# Processing.net
KiCad netlist of a schematic drawn in Altium Designer
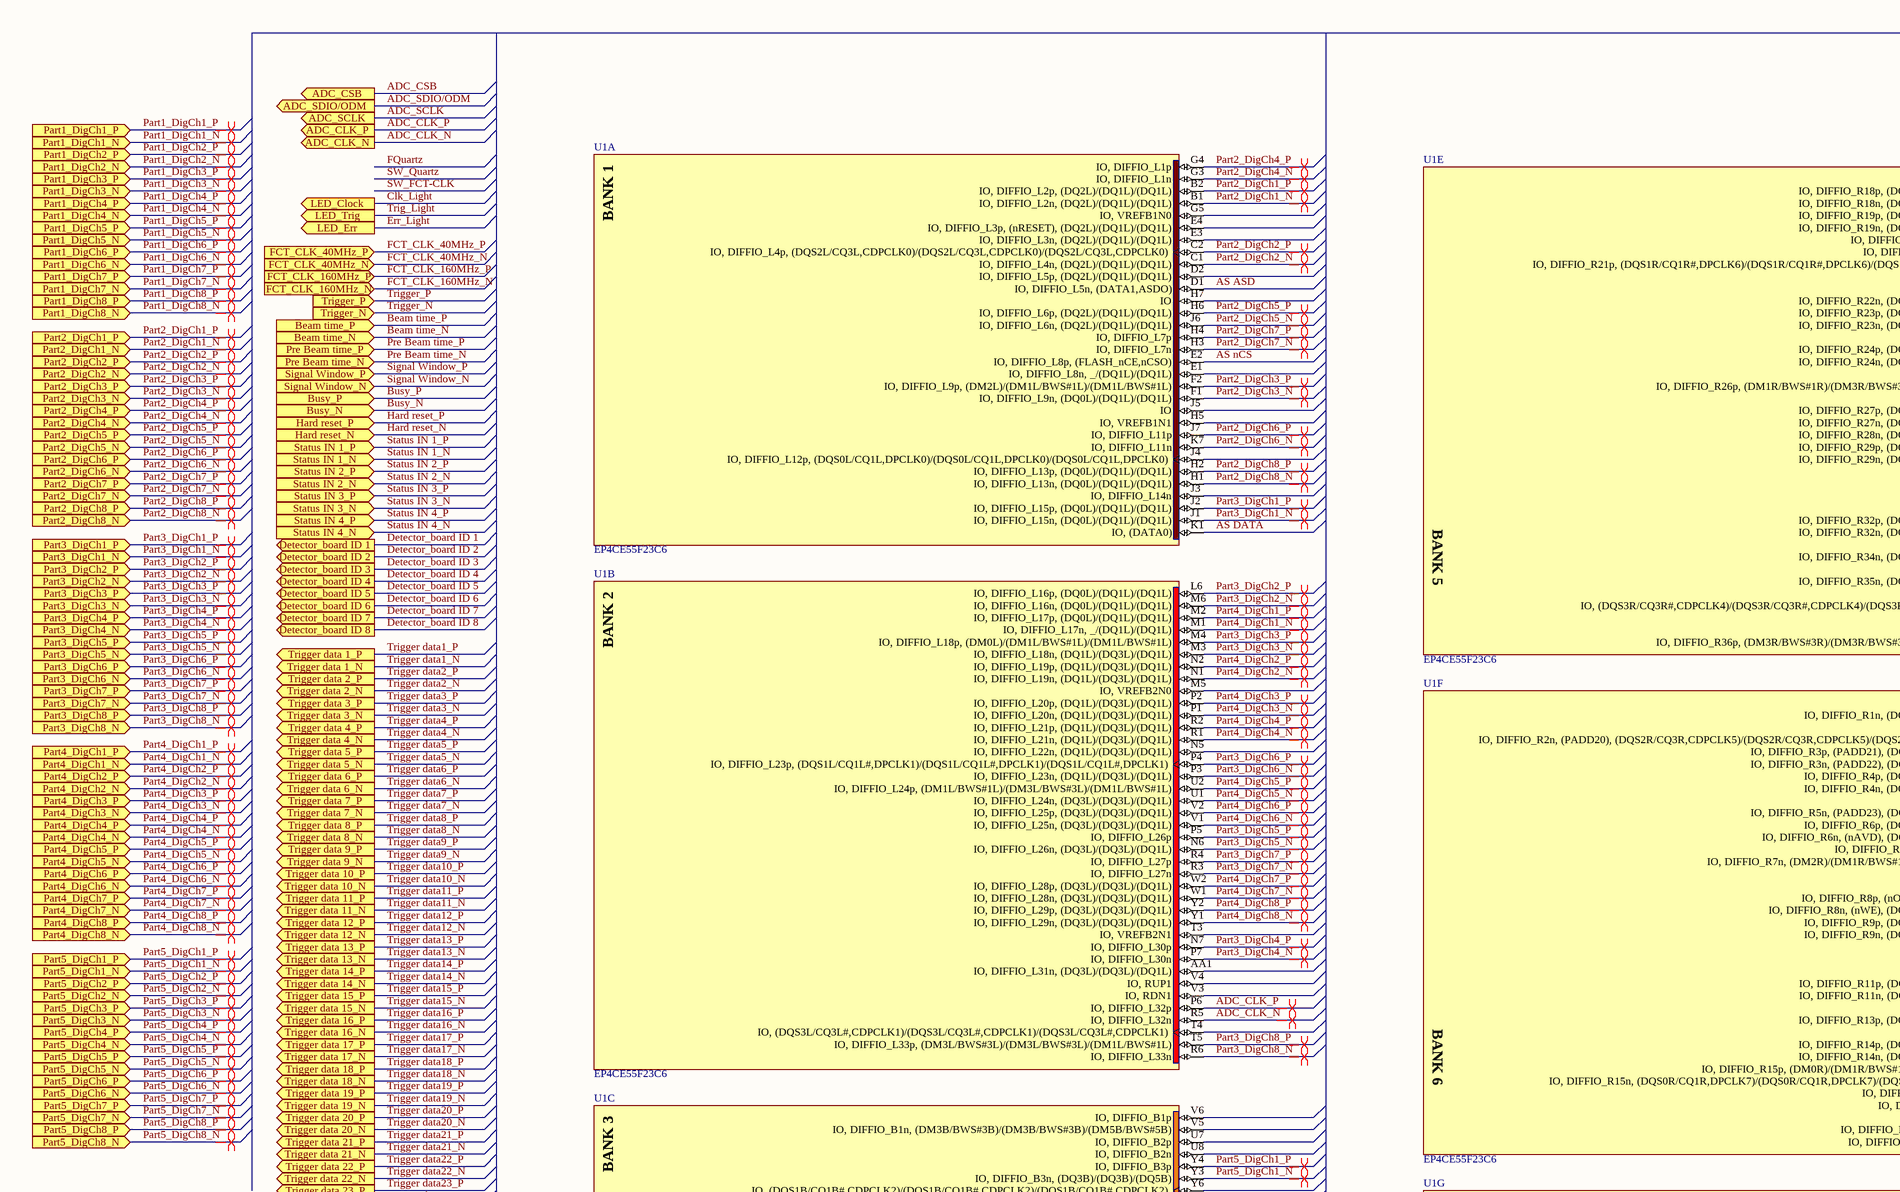
[diagram p0: Processing.SchDoc, top left]
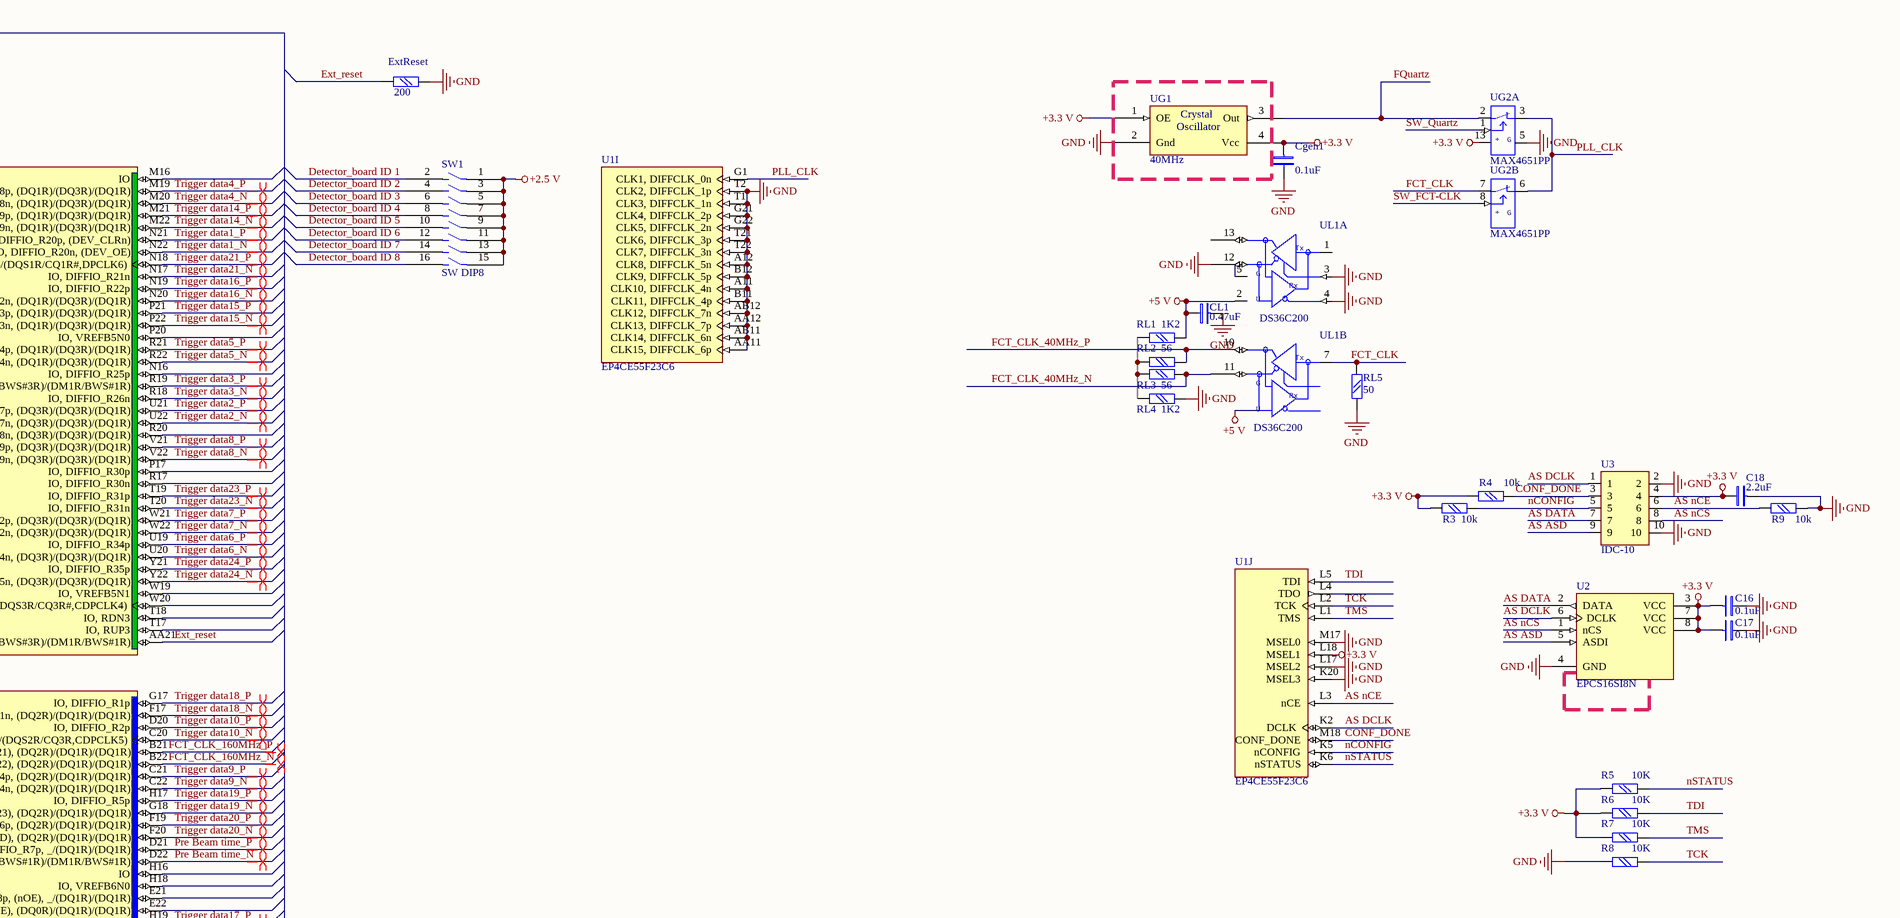
[diagram p1: Processing.SchDoc, top right]
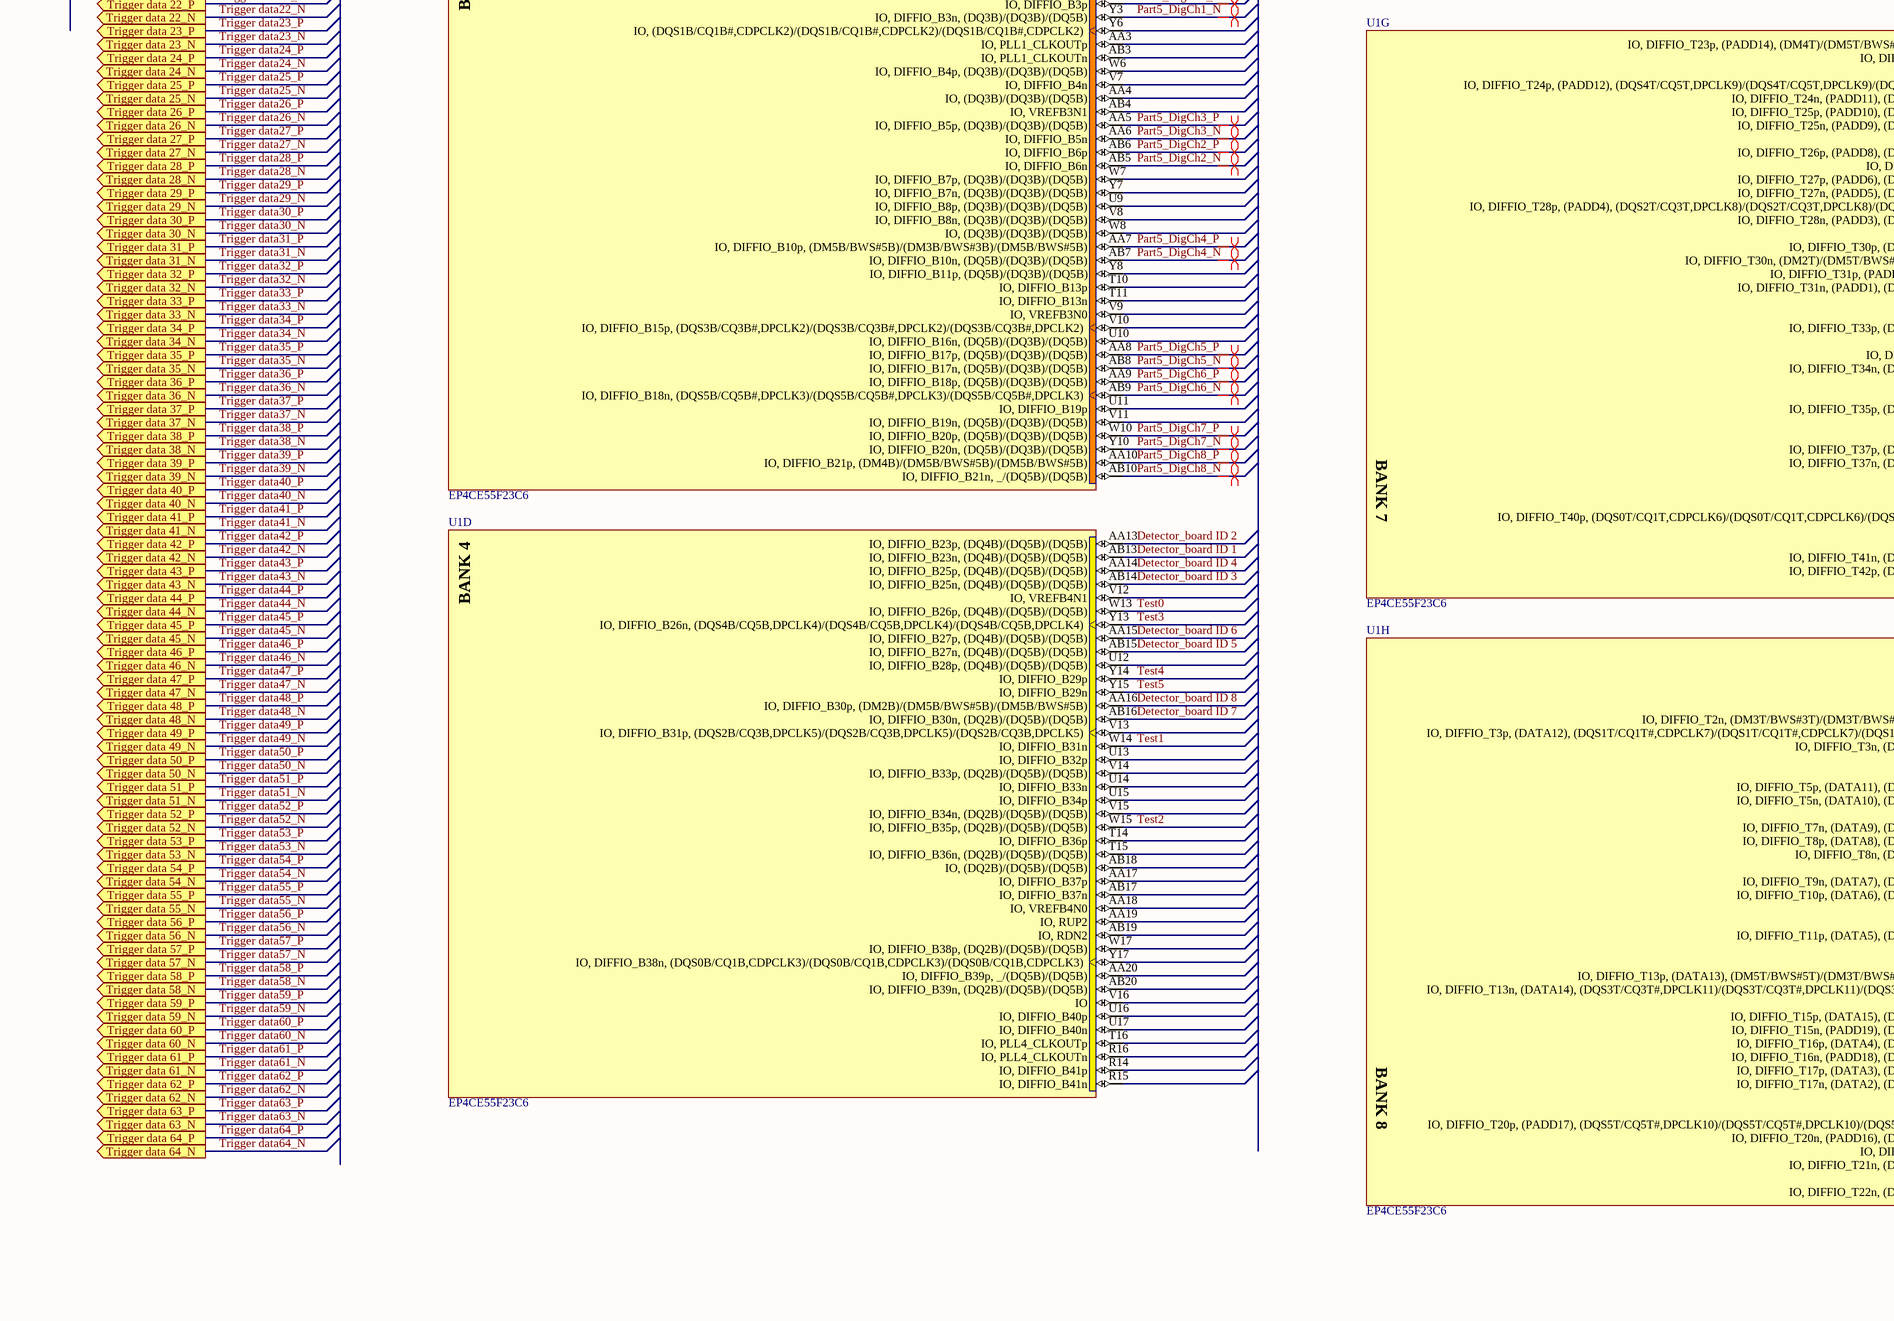
[diagram p2: Processing.SchDoc, bottom left]
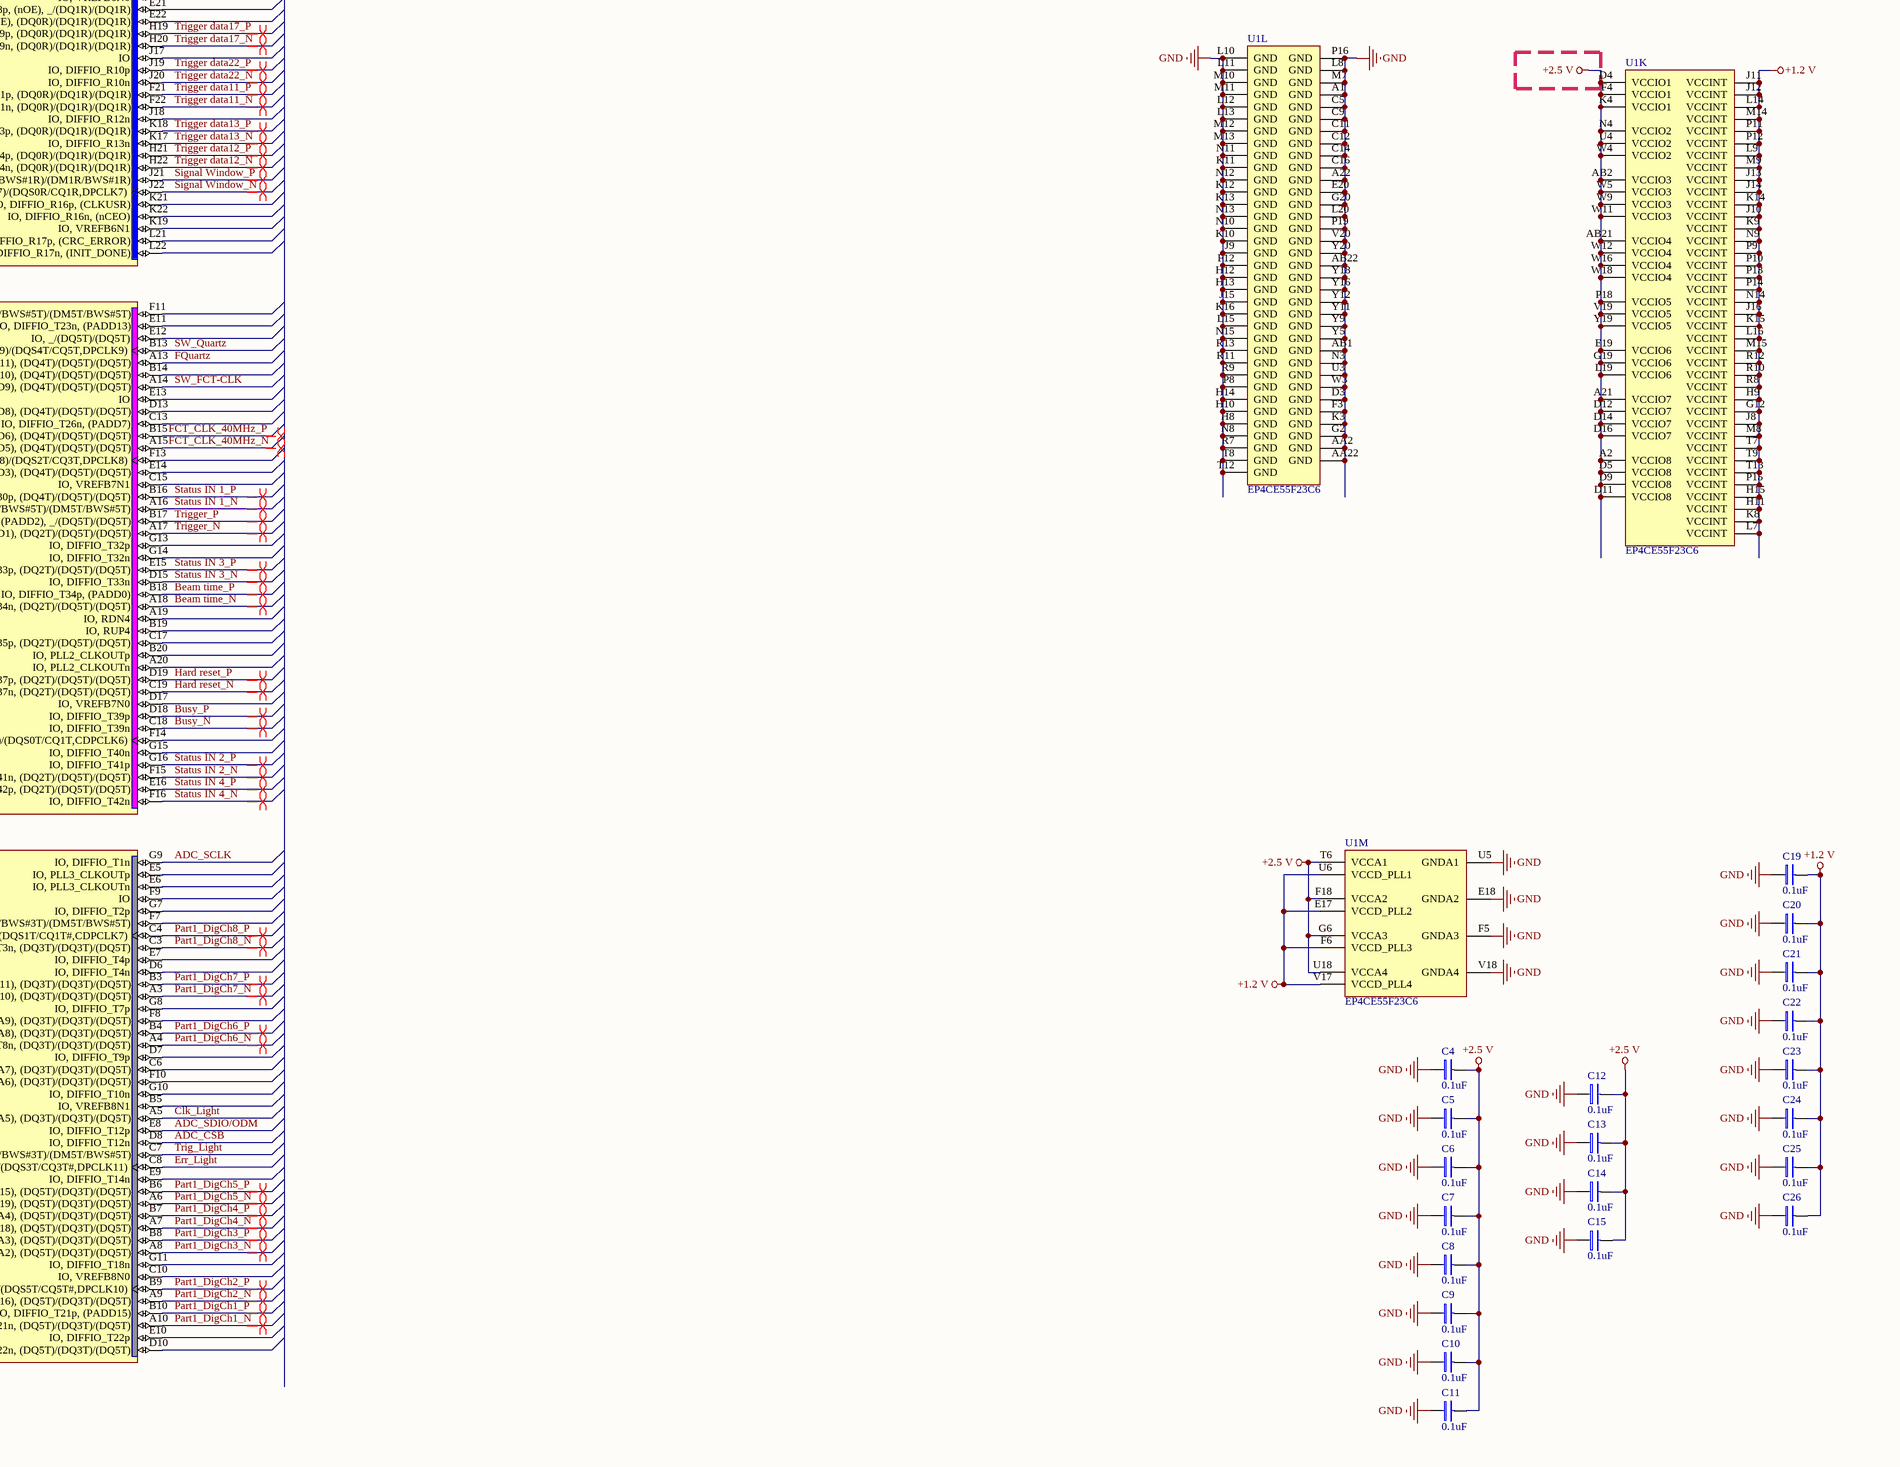
[diagram p3: Processing.SchDoc, bottom right]

(export (version "E")
  (design (tool "Eeschema 10.0.6"))
  (components
    (comp (ref "C4") (value "0.1uF") (footprint "chip0603") (libsource (lib "*") (part "C")))
    (comp (ref "C5") (value "0.1uF") (footprint "chip0603") (libsource (lib "*") (part "C")))
    (comp (ref "C6") (value "0.1uF") (footprint "chip0603") (libsource (lib "*") (part "C")))
    (comp (ref "C7") (value "0.1uF") (footprint "chip0603") (libsource (lib "*") (part "C")))
    (comp (ref "C8") (value "0.1uF") (footprint "chip0603") (libsource (lib "*") (part "C")))
    (comp (ref "C9") (value "0.1uF") (footprint "chip0603") (libsource (lib "*") (part "C")))
    (comp (ref "C10") (value "0.1uF") (footprint "chip0603") (libsource (lib "*") (part "C")))
    (comp (ref "C11") (value "0.1uF") (footprint "chip0603") (libsource (lib "*") (part "C")))
    (comp (ref "C12") (value "0.1uF") (footprint "chip0603") (libsource (lib "*") (part "C")))
    (comp (ref "C13") (value "0.1uF") (footprint "chip0603") (libsource (lib "*") (part "C")))
    (comp (ref "C14") (value "0.1uF") (footprint "chip0603") (libsource (lib "*") (part "C")))
    (comp (ref "C15") (value "0.1uF") (footprint "chip0603") (libsource (lib "*") (part "C")))
    (comp (ref "C16") (value "0.1uF") (footprint "chip0603") (libsource (lib "*") (part "C")))
    (comp (ref "C17") (value "0.1uF") (footprint "chip0603") (libsource (lib "*") (part "C")))
    (comp (ref "C18") (value "2.2uF") (footprint "chip0603") (libsource (lib "*") (part "C")))
    (comp (ref "C19") (value "0.1uF") (footprint "chip0603") (libsource (lib "*") (part "C")))
    (comp (ref "C20") (value "0.1uF") (footprint "chip0603") (libsource (lib "*") (part "C")))
    (comp (ref "C21") (value "0.1uF") (footprint "chip0603") (libsource (lib "*") (part "C")))
    (comp (ref "C22") (value "0.1uF") (footprint "chip0603") (libsource (lib "*") (part "C")))
    (comp (ref "C23") (value "0.1uF") (footprint "chip0603") (libsource (lib "*") (part "C")))
    (comp (ref "C24") (value "0.1uF") (footprint "chip0603") (libsource (lib "*") (part "C")))
    (comp (ref "C25") (value "0.1uF") (footprint "chip0603") (libsource (lib "*") (part "C")))
    (comp (ref "C26") (value "0.1uF") (footprint "chip0603") (libsource (lib "*") (part "C")))
    (comp (ref "Cgen1") (value "0.1uF") (footprint "chip0603") (libsource (lib "") (part "C_1")))
    (comp (ref "CL1") (value "0.47uF") (footprint "chip0603") (libsource (lib "") (part "C_1")))
    (comp (ref "ExtReset") (value "200") (footprint "chip0603") (libsource (lib "*") (part "R")))
    (comp (ref "R3") (value "10k") (footprint "chip0603") (libsource (lib "") (part "R_1")))
    (comp (ref "R4") (value "10k") (footprint "chip0603") (libsource (lib "") (part "R_1")))
    (comp (ref "R5") (value "10K") (footprint "chip0603") (libsource (lib "") (part "R_1")))
    (comp (ref "R6") (value "10K") (footprint "chip0603") (libsource (lib "") (part "R_1")))
    (comp (ref "R7") (value "10K") (footprint "chip0603") (libsource (lib "") (part "R_1")))
    (comp (ref "R8") (value "10K") (footprint "chip0603") (libsource (lib "") (part "R_1")))
    (comp (ref "R9") (value "10k") (footprint "chip0603") (libsource (lib "") (part "R_1")))
    (comp (ref "RL1") (value "1K2") (footprint "chip0603") (libsource (lib "*") (part "R")))
    (comp (ref "RL2") (value "56") (footprint "chip0603") (libsource (lib "*") (part "R")))
    (comp (ref "RL3") (value "56") (footprint "chip0603") (libsource (lib "*") (part "R")))
    (comp (ref "RL4") (value "1K2") (footprint "chip0603") (libsource (lib "*") (part "R")))
    (comp (ref "RL5") (value "50") (footprint "chip0603") (libsource (lib "*") (part "R")))
    (comp (ref "SW1") (value "SW DIP8") (footprint "SWD4-8") (libsource (lib "vDevice") (part "SW DIP8")))
    (comp (ref "U1")
      (value "EP4CE55F23C6")
      (footprint "FBGA484")
      (fields (field (name "PUBLISHER") "Altium Limited"))
      (libsource (lib "") (part "EP4CE55F23C6_1"))
    )
    (comp (ref "U2")
      (value "EPCS16SI8N")
      (footprint "SOIC8_N")
      (fields (field (name "PUBLISHER") "Altium Limited"))
      (libsource (lib "Altera EPCS Configuration Device") (part "EPCS4SI8N"))
    )
    (comp (ref "U3") (value "IDC-10") (footprint "IDC10") (libsource (lib "vDevice") (part "IDC-10")))
    (comp (ref "UG1")
      (value "40MHz")
      (footprint "SG-636")
      (description "Crystal Oscillator (SMD)")
      (libsource (lib "*") (part "SG-636"))
    )
    (comp (ref "UG2") (value "MAX4651PP") (footprint "16SOIC150") (libsource (lib "*") (part "MAX4651PP")))
    (comp (ref "UL1") (value "DS36C200") (footprint "14SO200") (libsource (lib "*") (part "DS36C200")))
  )
  (nets
    (net (code "1") (name "+1.2 V") (class "Default")
      (node (ref "C19") (pin "2") (pinfunction "2_2") (pintype "passive"))
      (node (ref "C20") (pin "2") (pinfunction "2_2") (pintype "passive"))
      (node (ref "C21") (pin "2") (pinfunction "2_2") (pintype "passive"))
      (node (ref "C22") (pin "2") (pinfunction "2_2") (pintype "passive"))
      (node (ref "C23") (pin "2") (pinfunction "2_2") (pintype "passive"))
      (node (ref "C24") (pin "2") (pinfunction "2_2") (pintype "passive"))
      (node (ref "C25") (pin "2") (pinfunction "2_2") (pintype "passive"))
      (node (ref "C26") (pin "2") (pinfunction "2_2") (pintype "passive"))
      (node (ref "U1") (pin "E17") (pinfunction "VCCD_PLL2_E17") (pintype "power_in"))
      (node (ref "U1") (pin "F6") (pinfunction "VCCD_PLL3_F6") (pintype "power_in"))
      (node (ref "U1") (pin "G12") (pinfunction "VCCINT_G12") (pintype "power_in"))
      (node (ref "U1") (pin "H11") (pinfunction "VCCINT_H11") (pintype "power_in"))
      (node (ref "U1") (pin "H15") (pinfunction "VCCINT_H15") (pintype "power_in"))
      (node (ref "U1") (pin "H9") (pinfunction "VCCINT_H9") (pintype "power_in"))
      (node (ref "U1") (pin "J10") (pinfunction "VCCINT_J10") (pintype "power_in"))
      (node (ref "U1") (pin "J11") (pinfunction "VCCINT_J11") (pintype "power_in"))
      (node (ref "U1") (pin "J12") (pinfunction "VCCINT_J12") (pintype "power_in"))
      (node (ref "U1") (pin "J13") (pinfunction "VCCINT_J13") (pintype "power_in"))
      (node (ref "U1") (pin "J14") (pinfunction "VCCINT_J14") (pintype "power_in"))
      (node (ref "U1") (pin "J16") (pinfunction "VCCINT_J16") (pintype "power_in"))
      (node (ref "U1") (pin "J8") (pinfunction "VCCINT_J8") (pintype "power_in"))
      (node (ref "U1") (pin "K14") (pinfunction "VCCINT_K14") (pintype "power_in"))
      (node (ref "U1") (pin "K15") (pinfunction "VCCINT_K15") (pintype "power_in"))
      (node (ref "U1") (pin "K8") (pinfunction "VCCINT_K8") (pintype "power_in"))
      (node (ref "U1") (pin "K9") (pinfunction "VCCINT_K9") (pintype "power_in"))
      (node (ref "U1") (pin "L14") (pinfunction "VCCINT_L14") (pintype "power_in"))
      (node (ref "U1") (pin "L16") (pinfunction "VCCINT_L16") (pintype "power_in"))
      (node (ref "U1") (pin "L7") (pinfunction "VCCINT_L7") (pintype "power_in"))
      (node (ref "U1") (pin "L9") (pinfunction "VCCINT_L9") (pintype "power_in"))
      (node (ref "U1") (pin "M14") (pinfunction "VCCINT_M14") (pintype "power_in"))
      (node (ref "U1") (pin "M15") (pinfunction "VCCINT_M15") (pintype "power_in"))
      (node (ref "U1") (pin "M8") (pinfunction "VCCINT_M8") (pintype "power_in"))
      (node (ref "U1") (pin "M9") (pinfunction "VCCINT_M9") (pintype "power_in"))
      (node (ref "U1") (pin "N14") (pinfunction "VCCINT_N14") (pintype "power_in"))
      (node (ref "U1") (pin "N9") (pinfunction "VCCINT_N9") (pintype "power_in"))
      (node (ref "U1") (pin "P10") (pinfunction "VCCINT_P10") (pintype "power_in"))
      (node (ref "U1") (pin "P11") (pinfunction "VCCINT_P11") (pintype "power_in"))
      (node (ref "U1") (pin "P12") (pinfunction "VCCINT_P12") (pintype "power_in"))
      (node (ref "U1") (pin "P13") (pinfunction "VCCINT_P13") (pintype "power_in"))
      (node (ref "U1") (pin "P14") (pinfunction "VCCINT_P14") (pintype "power_in"))
      (node (ref "U1") (pin "P15") (pinfunction "VCCINT_P15") (pintype "power_in"))
      (node (ref "U1") (pin "P9") (pinfunction "VCCINT_P9") (pintype "power_in"))
      (node (ref "U1") (pin "R10") (pinfunction "VCCINT_R10") (pintype "power_in"))
      (node (ref "U1") (pin "R12") (pinfunction "VCCINT_R12") (pintype "power_in"))
      (node (ref "U1") (pin "R8") (pinfunction "VCCINT_R8") (pintype "power_in"))
      (node (ref "U1") (pin "T13") (pinfunction "VCCINT_T13") (pintype "power_in"))
      (node (ref "U1") (pin "T7") (pinfunction "VCCINT_T7") (pintype "power_in"))
      (node (ref "U1") (pin "T9") (pinfunction "VCCINT_T9") (pintype "power_in"))
      (node (ref "U1") (pin "U6") (pinfunction "VCCD_PLL1_U6") (pintype "power_in"))
      (node (ref "U1") (pin "V17") (pinfunction "VCCD_PLL4_V17") (pintype "power_in"))
    )
    (net (code "2") (name "+2.5 V") (class "Default")
      (node (ref "C10") (pin "2") (pinfunction "2_2") (pintype "passive"))
      (node (ref "C11") (pin "2") (pinfunction "2_2") (pintype "passive"))
      (node (ref "C12") (pin "2") (pinfunction "2_2") (pintype "passive"))
      (node (ref "C13") (pin "2") (pinfunction "2_2") (pintype "passive"))
      (node (ref "C14") (pin "2") (pinfunction "2_2") (pintype "passive"))
      (node (ref "C15") (pin "2") (pinfunction "2_2") (pintype "passive"))
      (node (ref "C4") (pin "2") (pinfunction "2_2") (pintype "passive"))
      (node (ref "C5") (pin "2") (pinfunction "2_2") (pintype "passive"))
      (node (ref "C6") (pin "2") (pinfunction "2_2") (pintype "passive"))
      (node (ref "C7") (pin "2") (pinfunction "2_2") (pintype "passive"))
      (node (ref "C8") (pin "2") (pinfunction "2_2") (pintype "passive"))
      (node (ref "C9") (pin "2") (pinfunction "2_2") (pintype "passive"))
      (node (ref "SW1") (pin "1") (pinfunction "1_1") (pintype "passive"))
      (node (ref "SW1") (pin "11") (pinfunction "11_11") (pintype "passive"))
      (node (ref "SW1") (pin "13") (pinfunction "13_13") (pintype "passive"))
      (node (ref "SW1") (pin "15") (pinfunction "15_15") (pintype "passive"))
      (node (ref "SW1") (pin "3") (pinfunction "3_3") (pintype "passive"))
      (node (ref "SW1") (pin "5") (pinfunction "5_5") (pintype "passive"))
      (node (ref "SW1") (pin "7") (pinfunction "7_7") (pintype "passive"))
      (node (ref "SW1") (pin "9") (pinfunction "9_9") (pintype "passive"))
      (node (ref "U1") (pin "A2") (pinfunction "VCCIO8_A2") (pintype "power_in"))
      (node (ref "U1") (pin "A21") (pinfunction "VCCIO7_A21") (pintype "power_in"))
      (node (ref "U1") (pin "AB2") (pinfunction "VCCIO3_AB2") (pintype "power_in"))
      (node (ref "U1") (pin "AB21") (pinfunction "VCCIO4_AB21") (pintype "power_in"))
      (node (ref "U1") (pin "D11") (pinfunction "VCCIO8_D11") (pintype "power_in"))
      (node (ref "U1") (pin "D12") (pinfunction "VCCIO7_D12") (pintype "power_in"))
      (node (ref "U1") (pin "D14") (pinfunction "VCCIO7_D14") (pintype "power_in"))
      (node (ref "U1") (pin "D16") (pinfunction "VCCIO7_D16") (pintype "power_in"))
      (node (ref "U1") (pin "D4") (pinfunction "VCCIO1_D4") (pintype "power_in"))
      (node (ref "U1") (pin "D5") (pinfunction "VCCIO8_D5") (pintype "power_in"))
      (node (ref "U1") (pin "D9") (pinfunction "VCCIO8_D9") (pintype "power_in"))
      (node (ref "U1") (pin "E19") (pinfunction "VCCIO6_E19") (pintype "power_in"))
      (node (ref "U1") (pin "F18") (pinfunction "VCCA2_F18") (pintype "power_in"))
      (node (ref "U1") (pin "F4") (pinfunction "VCCIO1_F4") (pintype "power_in"))
      (node (ref "U1") (pin "G19") (pinfunction "VCCIO6_G19") (pintype "power_in"))
      (node (ref "U1") (pin "G6") (pinfunction "VCCA3_G6") (pintype "power_in"))
      (node (ref "U1") (pin "K4") (pinfunction "VCCIO1_K4") (pintype "power_in"))
      (node (ref "U1") (pin "L19") (pinfunction "VCCIO6_L19") (pintype "power_in"))
      (node (ref "U1") (pin "N4") (pinfunction "VCCIO2_N4") (pintype "power_in"))
      (node (ref "U1") (pin "P18") (pinfunction "VCCIO5_P18") (pintype "power_in"))
      (node (ref "U1") (pin "T6") (pinfunction "VCCA1_T6") (pintype "power_in"))
      (node (ref "U1") (pin "U18") (pinfunction "VCCA4_U18") (pintype "power_in"))
      (node (ref "U1") (pin "U4") (pinfunction "VCCIO2_U4") (pintype "power_in"))
      (node (ref "U1") (pin "V19") (pinfunction "VCCIO5_V19") (pintype "power_in"))
      (node (ref "U1") (pin "W11") (pinfunction "VCCIO3_W11") (pintype "power_in"))
      (node (ref "U1") (pin "W12") (pinfunction "VCCIO4_W12") (pintype "power_in"))
      (node (ref "U1") (pin "W16") (pinfunction "VCCIO4_W16") (pintype "power_in"))
      (node (ref "U1") (pin "W18") (pinfunction "VCCIO4_W18") (pintype "power_in"))
      (node (ref "U1") (pin "W4") (pinfunction "VCCIO2_W4") (pintype "power_in"))
      (node (ref "U1") (pin "W5") (pinfunction "VCCIO3_W5") (pintype "power_in"))
      (node (ref "U1") (pin "W9") (pinfunction "VCCIO3_W9") (pintype "power_in"))
      (node (ref "U1") (pin "Y19") (pinfunction "VCCIO5_Y19") (pintype "power_in"))
    )
    (net (code "3") (name "+3.3 V") (class "Default")
      (node (ref "C16") (pin "2") (pinfunction "2_2") (pintype "passive"))
      (node (ref "C17") (pin "2") (pinfunction "2_2") (pintype "passive"))
      (node (ref "C18") (pin "1") (pinfunction "1_1") (pintype "passive"))
      (node (ref "Cgen1") (pin "2") (pinfunction "2_2") (pintype "passive"))
      (node (ref "R3") (pin "1") (pinfunction "1_1") (pintype "passive"))
      (node (ref "R4") (pin "1") (pinfunction "1_1") (pintype "passive"))
      (node (ref "R5") (pin "1") (pinfunction "1_1") (pintype "passive"))
      (node (ref "R6") (pin "1") (pinfunction "1_1") (pintype "passive"))
      (node (ref "R7") (pin "1") (pinfunction "1_1") (pintype "passive"))
      (node (ref "U1") (pin "L18") (pinfunction "MSEL1_L18") (pintype "input"))
      (node (ref "U2") (pin "3") (pinfunction "VCC_3") (pintype "power_in"))
      (node (ref "U2") (pin "7") (pinfunction "VCC_7") (pintype "power_in"))
      (node (ref "U2") (pin "8") (pinfunction "VCC_8") (pintype "power_in"))
      (node (ref "U3") (pin "4") (pinfunction "4_4") (pintype "bidirectional"))
      (node (ref "UG1") (pin "1") (pinfunction "OE_1") (pintype "input"))
      (node (ref "UG1") (pin "4") (pinfunction "Vcc_4") (pintype "power_in"))
      (node (ref "UG2") (pin "13") (pinfunction "VCC_13") (pintype "passive"))
    )
    (net (code "4") (name "+5 V") (class "Default")
      (node (ref "CL1") (pin "1") (pinfunction "1_1") (pintype "passive"))
      (node (ref "RL1") (pin "2") (pinfunction "2_2") (pintype "passive"))
      (node (ref "UL1") (pin "2") (pinfunction "VCC_2") (pintype "passive"))
    )
    (net (code "5") (name "/ADC_CLK_N") (class "Default")
      (node (ref "U1") (pin "R5") (pinfunction "IO,_DIFFIO_L32n_R5") (pintype "bidirectional"))
    )
    (net (code "6") (name "/ADC_CLK_P") (class "Default")
      (node (ref "U1") (pin "P6") (pinfunction "IO,_DIFFIO_L32p_P6") (pintype "bidirectional"))
    )
    (net (code "7") (name "/ADC_CSB") (class "Default")
      (node (ref "U1") (pin "D8") (pinfunction "IO,_DIFFIO_T12n_D8") (pintype "bidirectional"))
    )
    (net (code "8") (name "/ADC_SCLK") (class "Default")
      (node (ref "U1") (pin "G9") (pinfunction "IO,_DIFFIO_T1n_G9") (pintype "bidirectional"))
    )
    (net (code "9") (name "/ADC_SDIO{slash}ODM") (class "Default")
      (node (ref "U1") (pin "E8") (pinfunction "IO,_DIFFIO_T12p_E8") (pintype "bidirectional"))
    )
    (net (code "10") (name "/AS ASD") (class "Default")
      (node (ref "U1") (pin "D1") (pinfunction "IO,_DIFFIO_L5n,_(DATA1,ASDO)_D1") (pintype "bidirectional"))
      (node (ref "U2") (pin "5") (pinfunction "ASDI_5") (pintype "input"))
      (node (ref "U3") (pin "9") (pinfunction "9_9") (pintype "bidirectional"))
    )
    (net (code "11") (name "/AS DATA") (class "Default")
      (node (ref "U1") (pin "K1") (pinfunction "IO,_(DATA0)_K1") (pintype "bidirectional"))
      (node (ref "U2") (pin "2") (pinfunction "DATA_2") (pintype "output"))
      (node (ref "U3") (pin "7") (pinfunction "7_7") (pintype "bidirectional"))
    )
    (net (code "12") (name "/AS DCLK") (class "Default")
      (node (ref "U1") (pin "K2") (pinfunction "DCLK_K2") (pintype "bidirectional"))
      (node (ref "U2") (pin "6") (pinfunction "DCLK_6") (pintype "input"))
      (node (ref "U3") (pin "1") (pinfunction "1_1") (pintype "bidirectional"))
    )
    (net (code "13") (name "/AS nCE") (class "Default")
      (node (ref "R9") (pin "1") (pinfunction "1_1") (pintype "passive"))
      (node (ref "U1") (pin "L3") (pinfunction "nCE_L3") (pintype "input"))
      (node (ref "U3") (pin "6") (pinfunction "6_6") (pintype "bidirectional"))
    )
    (net (code "14") (name "/AS nCS") (class "Default")
      (node (ref "U1") (pin "E2") (pinfunction "IO,_DIFFIO_L8p,_(FLASH_nCE,nCSO)_E2") (pintype "bidirectional"))
      (node (ref "U2") (pin "1") (pinfunction "nCS_1") (pintype "input"))
      (node (ref "U3") (pin "8") (pinfunction "8_8") (pintype "bidirectional"))
    )
    (net (code "15") (name "/Beam time_N") (class "Default")
      (node (ref "U1") (pin "A18") (pinfunction "IO,_DIFFIO_T34n,_(DQ2T)/(DQ5T)/(DQ5T)_A18") (pintype "bidirectional"))
    )
    (net (code "16") (name "/Beam time_P") (class "Default")
      (node (ref "U1") (pin "B18") (pinfunction "IO,_DIFFIO_T34p,_(PADD0)_B18") (pintype "bidirectional"))
    )
    (net (code "17") (name "/Busy_N") (class "Default")
      (node (ref "U1") (pin "C18") (pinfunction "IO,_DIFFIO_T39n_C18") (pintype "bidirectional"))
    )
    (net (code "18") (name "/Busy_P") (class "Default")
      (node (ref "U1") (pin "D18") (pinfunction "IO,_DIFFIO_T39p_D18") (pintype "bidirectional"))
    )
    (net (code "19") (name "/CONF_DONE") (class "Default")
      (node (ref "R4") (pin "2") (pinfunction "2_2") (pintype "passive"))
      (node (ref "U1") (pin "M18") (pinfunction "CONF_DONE_M18") (pintype "bidirectional"))
      (node (ref "U3") (pin "3") (pinfunction "3_3") (pintype "bidirectional"))
    )
    (net (code "20") (name "/Clk_Light") (class "Default")
      (node (ref "U1") (pin "A5") (pinfunction "IO,_DIFFIO_T11p,_(DATA5),_(DQ3T)/(DQ3T)/(DQ5T)_A5") (pintype "bidirectional"))
    )
    (net (code "21") (name "/Detector_board ID 1") (class "Default")
      (node (ref "SW1") (pin "2") (pinfunction "2_2") (pintype "passive"))
      (node (ref "U1") (pin "AB13") (pinfunction "IO,_DIFFIO_B23n,_(DQ4B)/(DQ5B)/(DQ5B)_AB13") (pintype "bidirectional"))
    )
    (net (code "22") (name "/Detector_board ID 2") (class "Default")
      (node (ref "SW1") (pin "4") (pinfunction "4_4") (pintype "passive"))
      (node (ref "U1") (pin "AA13") (pinfunction "IO,_DIFFIO_B23p,_(DQ4B)/(DQ5B)/(DQ5B)_AA13") (pintype "bidirectional"))
    )
    (net (code "23") (name "/Detector_board ID 3") (class "Default")
      (node (ref "SW1") (pin "6") (pinfunction "6_6") (pintype "passive"))
      (node (ref "U1") (pin "AB14") (pinfunction "IO,_DIFFIO_B25n,_(DQ4B)/(DQ5B)/(DQ5B)_AB14") (pintype "bidirectional"))
    )
    (net (code "24") (name "/Detector_board ID 4") (class "Default")
      (node (ref "SW1") (pin "8") (pinfunction "8_8") (pintype "passive"))
      (node (ref "U1") (pin "AA14") (pinfunction "IO,_DIFFIO_B25p,_(DQ4B)/(DQ5B)/(DQ5B)_AA14") (pintype "bidirectional"))
    )
    (net (code "25") (name "/Detector_board ID 5") (class "Default")
      (node (ref "SW1") (pin "10") (pinfunction "10_10") (pintype "passive"))
      (node (ref "U1") (pin "AB15") (pinfunction "IO,_DIFFIO_B27n,_(DQ4B)/(DQ5B)/(DQ5B)_AB15") (pintype "bidirectional"))
    )
    (net (code "26") (name "/Detector_board ID 6") (class "Default")
      (node (ref "SW1") (pin "12") (pinfunction "12_12") (pintype "passive"))
      (node (ref "U1") (pin "AA15") (pinfunction "IO,_DIFFIO_B27p,_(DQ4B)/(DQ5B)/(DQ5B)_AA15") (pintype "bidirectional"))
    )
    (net (code "27") (name "/Detector_board ID 7") (class "Default")
      (node (ref "SW1") (pin "14") (pinfunction "14_14") (pintype "passive"))
      (node (ref "U1") (pin "AB16") (pinfunction "IO,_DIFFIO_B30n,_(DQ2B)/(DQ5B)/(DQ5B)_AB16") (pintype "bidirectional"))
    )
    (net (code "28") (name "/Detector_board ID 8") (class "Default")
      (node (ref "SW1") (pin "16") (pinfunction "16_16") (pintype "passive"))
      (node (ref "U1") (pin "AA16") (pinfunction "IO,_DIFFIO_B30p,_(DM2B)/(DM5B/BWS#5B)/(DM5B/BWS#5B)_AA16") (pintype "bidirectional"))
    )
    (net (code "29") (name "/Err_Light") (class "Default")
      (node (ref "U1") (pin "C8") (pinfunction "IO,_DIFFIO_T13n,_(DATA14),_(DQS3T/CQ3T#,DPCLK11)/(DQS3T/CQ3T#,DPCLK11)/(DQS3T/CQ3T#,DPCLK11)_C8") (pintype "bidirectional"))
    )
    (net (code "30") (name "/Ext_reset") (class "Default")
      (node (ref "ExtReset") (pin "1") (pinfunction "1_1") (pintype "passive"))
      (node (ref "U1") (pin "AA21") (pinfunction "IO,_DIFFIO_R36p,_(DM3R/BWS#3R)/(DM3R/BWS#3R)/(DM1R/BWS#1R)_AA21") (pintype "bidirectional"))
    )
    (net (code "31") (name "/FCT_CLK") (class "Default")
      (node (ref "RL5") (pin "1") (pinfunction "1_1") (pintype "passive"))
      (node (ref "UG2") (pin "7") (pinfunction "IN_7") (pintype "bidirectional"))
      (node (ref "UL1") (pin "7") (pinfunction "DATA_7") (pintype "bidirectional"))
    )
    (net (code "32") (name "/FCT_CLK_40MHz_N") (class "Default")
      (node (ref "RL3") (pin "2") (pinfunction "2_2") (pintype "passive"))
      (node (ref "U1") (pin "A15") (pinfunction "IO,_DIFFIO_T27n,_(PADD5),_(DQ4T)/(DQ5T)/(DQ5T)_A15") (pintype "bidirectional"))
      (node (ref "UL1") (pin "11") (pinfunction "WIRE-_11") (pintype "bidirectional"))
    )
    (net (code "33") (name "/FCT_CLK_40MHz_P") (class "Default")
      (node (ref "RL2") (pin "2") (pinfunction "2_2") (pintype "passive"))
      (node (ref "U1") (pin "B15") (pinfunction "IO,_DIFFIO_T27p,_(PADD6),_(DQ4T)/(DQ5T)/(DQ5T)_B15") (pintype "bidirectional"))
      (node (ref "UL1") (pin "10") (pinfunction "WIRE+_10") (pintype "bidirectional"))
    )
    (net (code "34") (name "/FCT_CLK_160MHz_N") (class "Default")
      (node (ref "U1") (pin "B22") (pinfunction "IO,_DIFFIO_R3n,_(PADD22),_(DQ2R)/(DQ1R)/(DQ1R)_B22") (pintype "bidirectional"))
    )
    (net (code "35") (name "/FCT_CLK_160MHz_P") (class "Default")
      (node (ref "U1") (pin "B21") (pinfunction "IO,_DIFFIO_R3p,_(PADD21),_(DQ2R)/(DQ1R)/(DQ1R)_B21") (pintype "bidirectional"))
    )
    (net (code "36") (name "/FQuartz") (class "Default")
      (node (ref "U1") (pin "A13") (pinfunction "IO,_DIFFIO_T24n,_(PADD11),_(DQ4T)/(DQ5T)/(DQ5T)_A13") (pintype "bidirectional"))
      (node (ref "UG1") (pin "3") (pinfunction "Out_3") (pintype "output"))
      (node (ref "UG2") (pin "2") (pinfunction "IN_2") (pintype "bidirectional"))
    )
    (net (code "37") (name "/Hard reset_N") (class "Default")
      (node (ref "U1") (pin "C19") (pinfunction "IO,_DIFFIO_T37n,_(DQ2T)/(DQ5T)/(DQ5T)_C19") (pintype "bidirectional"))
    )
    (net (code "38") (name "/Hard reset_P") (class "Default")
      (node (ref "U1") (pin "D19") (pinfunction "IO,_DIFFIO_T37p,_(DQ2T)/(DQ5T)/(DQ5T)_D19") (pintype "bidirectional"))
    )
    (net (code "39") (name "/PLL_CLK") (class "Default")
      (node (ref "U1") (pin "G1") (pinfunction "CLK1,_DIFFCLK_0n_G1") (pintype "input"))
      (node (ref "UG2") (pin "3") (pinfunction "OUT_3") (pintype "bidirectional"))
      (node (ref "UG2") (pin "6") (pinfunction "OUT_6") (pintype "bidirectional"))
    )
    (net (code "40") (name "/Part1_DigCh1_N") (class "Default")
      (node (ref "U1") (pin "A10") (pinfunction "IO,_DIFFIO_T21n,_(DQ5T)/(DQ3T)/(DQ5T)_A10") (pintype "bidirectional"))
    )
    (net (code "41") (name "/Part1_DigCh1_P") (class "Default")
      (node (ref "U1") (pin "B10") (pinfunction "IO,_DIFFIO_T21p,_(PADD15)_B10") (pintype "bidirectional"))
    )
    (net (code "42") (name "/Part1_DigCh2_N") (class "Default")
      (node (ref "U1") (pin "A9") (pinfunction "IO,_DIFFIO_T20n,_(PADD16),_(DQ5T)/(DQ3T)/(DQ5T)_A9") (pintype "bidirectional"))
    )
    (net (code "43") (name "/Part1_DigCh2_P") (class "Default")
      (node (ref "U1") (pin "B9") (pinfunction "IO,_DIFFIO_T20p,_(PADD17),_(DQS5T/CQ5T#,DPCLK10)/(DQS5T/CQ5T#,DPCLK10)/(DQS5T/CQ5T#,DPCLK10)_B9") (pintype "bidirectional"))
    )
    (net (code "44") (name "/Part1_DigCh3_N") (class "Default")
      (node (ref "U1") (pin "A8") (pinfunction "IO,_DIFFIO_T17n,_(DATA2),_(DQ5T)/(DQ3T)/(DQ5T)_A8") (pintype "bidirectional"))
    )
    (net (code "45") (name "/Part1_DigCh3_P") (class "Default")
      (node (ref "U1") (pin "B8") (pinfunction "IO,_DIFFIO_T17p,_(DATA3),_(DQ5T)/(DQ3T)/(DQ5T)_B8") (pintype "bidirectional"))
    )
    (net (code "46") (name "/Part1_DigCh4_N") (class "Default")
      (node (ref "U1") (pin "A7") (pinfunction "IO,_DIFFIO_T16n,_(PADD18),_(DQ5T)/(DQ3T)/(DQ5T)_A7") (pintype "bidirectional"))
    )
    (net (code "47") (name "/Part1_DigCh4_P") (class "Default")
      (node (ref "U1") (pin "B7") (pinfunction "IO,_DIFFIO_T16p,_(DATA4),_(DQ5T)/(DQ3T)/(DQ5T)_B7") (pintype "bidirectional"))
    )
    (net (code "48") (name "/Part1_DigCh5_N") (class "Default")
      (node (ref "U1") (pin "A6") (pinfunction "IO,_DIFFIO_T15n,_(PADD19),_(DQ5T)/(DQ3T)/(DQ5T)_A6") (pintype "bidirectional"))
    )
    (net (code "49") (name "/Part1_DigCh5_P") (class "Default")
      (node (ref "U1") (pin "B6") (pinfunction "IO,_DIFFIO_T15p,_(DATA15),_(DQ5T)/(DQ3T)/(DQ5T)_B6") (pintype "bidirectional"))
    )
    (net (code "50") (name "/Part1_DigCh6_N") (class "Default")
      (node (ref "U1") (pin "A4") (pinfunction "IO,_DIFFIO_T8n,_(DQ3T)/(DQ3T)/(DQ5T)_A4") (pintype "bidirectional"))
    )
    (net (code "51") (name "/Part1_DigCh6_P") (class "Default")
      (node (ref "U1") (pin "B4") (pinfunction "IO,_DIFFIO_T8p,_(DATA8),_(DQ3T)/(DQ3T)/(DQ5T)_B4") (pintype "bidirectional"))
    )
    (net (code "52") (name "/Part1_DigCh7_N") (class "Default")
      (node (ref "U1") (pin "A3") (pinfunction "IO,_DIFFIO_T5n,_(DATA10),_(DQ3T)/(DQ3T)/(DQ5T)_A3") (pintype "bidirectional"))
    )
    (net (code "53") (name "/Part1_DigCh7_P") (class "Default")
      (node (ref "U1") (pin "B3") (pinfunction "IO,_DIFFIO_T5p,_(DATA11),_(DQ3T)/(DQ3T)/(DQ5T)_B3") (pintype "bidirectional"))
    )
    (net (code "54") (name "/Part1_DigCh8_N") (class "Default")
      (node (ref "U1") (pin "C3") (pinfunction "IO,_DIFFIO_T3n,_(DQ3T)/(DQ3T)/(DQ5T)_C3") (pintype "bidirectional"))
    )
    (net (code "55") (name "/Part1_DigCh8_P") (class "Default")
      (node (ref "U1") (pin "C4") (pinfunction "IO,_DIFFIO_T3p,_(DATA12),_(DQS1T/CQ1T#,CDPCLK7)/(DQS1T/CQ1T#,CDPCLK7)/(DQS1T/CQ1T#,CDPCLK7)_C4") (pintype "bidirectional"))
    )
    (net (code "56") (name "/Part2_DigCh1_N") (class "Default")
      (node (ref "U1") (pin "B1") (pinfunction "IO,_DIFFIO_L2n,_(DQ2L)/(DQ1L)/(DQ1L)_B1") (pintype "bidirectional"))
    )
    (net (code "57") (name "/Part2_DigCh1_P") (class "Default")
      (node (ref "U1") (pin "B2") (pinfunction "IO,_DIFFIO_L2p,_(DQ2L)/(DQ1L)/(DQ1L)_B2") (pintype "bidirectional"))
    )
    (net (code "58") (name "/Part2_DigCh2_N") (class "Default")
      (node (ref "U1") (pin "C1") (pinfunction "IO,_DIFFIO_L4n,_(DQ2L)/(DQ1L)/(DQ1L)_C1") (pintype "bidirectional"))
    )
    (net (code "59") (name "/Part2_DigCh2_P") (class "Default")
      (node (ref "U1") (pin "C2") (pinfunction "IO,_DIFFIO_L4p,_(DQS2L/CQ3L,CDPCLK0)/(DQS2L/CQ3L,CDPCLK0)/(DQS2L/CQ3L,CDPCLK0)_C2") (pintype "bidirectional"))
    )
    (net (code "60") (name "/Part2_DigCh3_N") (class "Default")
      (node (ref "U1") (pin "F1") (pinfunction "IO,_DIFFIO_L9n,_(DQ0L)/(DQ1L)/(DQ1L)_F1") (pintype "bidirectional"))
    )
    (net (code "61") (name "/Part2_DigCh3_P") (class "Default")
      (node (ref "U1") (pin "F2") (pinfunction "IO,_DIFFIO_L9p,_(DM2L)/(DM1L/BWS#1L)/(DM1L/BWS#1L)_F2") (pintype "bidirectional"))
    )
    (net (code "62") (name "/Part2_DigCh4_N") (class "Default")
      (node (ref "U1") (pin "G3") (pinfunction "IO,_DIFFIO_L1n_G3") (pintype "bidirectional"))
    )
    (net (code "63") (name "/Part2_DigCh4_P") (class "Default")
      (node (ref "U1") (pin "G4") (pinfunction "IO,_DIFFIO_L1p_G4") (pintype "bidirectional"))
    )
    (net (code "64") (name "/Part2_DigCh5_N") (class "Default")
      (node (ref "U1") (pin "J6") (pinfunction "IO,_DIFFIO_L6n,_(DQ2L)/(DQ1L)/(DQ1L)_J6") (pintype "bidirectional"))
    )
    (net (code "65") (name "/Part2_DigCh5_P") (class "Default")
      (node (ref "U1") (pin "H6") (pinfunction "IO,_DIFFIO_L6p,_(DQ2L)/(DQ1L)/(DQ1L)_H6") (pintype "bidirectional"))
    )
    (net (code "66") (name "/Part2_DigCh6_N") (class "Default")
      (node (ref "U1") (pin "K7") (pinfunction "IO,_DIFFIO_L11n_K7") (pintype "bidirectional"))
    )
    (net (code "67") (name "/Part2_DigCh6_P") (class "Default")
      (node (ref "U1") (pin "J7") (pinfunction "IO,_DIFFIO_L11p_J7") (pintype "bidirectional"))
    )
    (net (code "68") (name "/Part2_DigCh7_N") (class "Default")
      (node (ref "U1") (pin "H3") (pinfunction "IO,_DIFFIO_L7n_H3") (pintype "bidirectional"))
    )
    (net (code "69") (name "/Part2_DigCh7_P") (class "Default")
      (node (ref "U1") (pin "H4") (pinfunction "IO,_DIFFIO_L7p_H4") (pintype "bidirectional"))
    )
    (net (code "70") (name "/Part2_DigCh8_N") (class "Default")
      (node (ref "U1") (pin "H1") (pinfunction "IO,_DIFFIO_L13n,_(DQ0L)/(DQ1L)/(DQ1L)_H1") (pintype "bidirectional"))
    )
    (net (code "71") (name "/Part2_DigCh8_P") (class "Default")
      (node (ref "U1") (pin "H2") (pinfunction "IO,_DIFFIO_L13p,_(DQ0L)/(DQ1L)/(DQ1L)_H2") (pintype "bidirectional"))
    )
    (net (code "72") (name "/Part3_DigCh1_N") (class "Default")
      (node (ref "U1") (pin "J1") (pinfunction "IO,_DIFFIO_L15n,_(DQ0L)/(DQ1L)/(DQ1L)_J1") (pintype "bidirectional"))
    )
    (net (code "73") (name "/Part3_DigCh1_P") (class "Default")
      (node (ref "U1") (pin "J2") (pinfunction "IO,_DIFFIO_L15p,_(DQ0L)/(DQ1L)/(DQ1L)_J2") (pintype "bidirectional"))
    )
    (net (code "74") (name "/Part3_DigCh2_N") (class "Default")
      (node (ref "U1") (pin "M6") (pinfunction "IO,_DIFFIO_L16n,_(DQ0L)/(DQ1L)/(DQ1L)_M6") (pintype "bidirectional"))
    )
    (net (code "75") (name "/Part3_DigCh2_P") (class "Default")
      (node (ref "U1") (pin "L6") (pinfunction "IO,_DIFFIO_L16p,_(DQ0L)/(DQ1L)/(DQ1L)_L6") (pintype "bidirectional"))
    )
    (net (code "76") (name "/Part3_DigCh3_N") (class "Default")
      (node (ref "U1") (pin "M3") (pinfunction "IO,_DIFFIO_L18n,_(DQ1L)/(DQ3L)/(DQ1L)_M3") (pintype "bidirectional"))
    )
    (net (code "77") (name "/Part3_DigCh3_P") (class "Default")
      (node (ref "U1") (pin "M4") (pinfunction "IO,_DIFFIO_L18p,_(DM0L)/(DM1L/BWS#1L)/(DM1L/BWS#1L)_M4") (pintype "bidirectional"))
    )
    (net (code "78") (name "/Part3_DigCh4_N") (class "Default")
      (node (ref "U1") (pin "P7") (pinfunction "IO,_DIFFIO_L30n_P7") (pintype "bidirectional"))
    )
    (net (code "79") (name "/Part3_DigCh4_P") (class "Default")
      (node (ref "U1") (pin "N7") (pinfunction "IO,_DIFFIO_L30p_N7") (pintype "bidirectional"))
    )
    (net (code "80") (name "/Part3_DigCh5_N") (class "Default")
      (node (ref "U1") (pin "N6") (pinfunction "IO,_DIFFIO_L26n,_(DQ3L)/(DQ3L)/(DQ1L)_N6") (pintype "bidirectional"))
    )
    (net (code "81") (name "/Part3_DigCh5_P") (class "Default")
      (node (ref "U1") (pin "P5") (pinfunction "IO,_DIFFIO_L26p_P5") (pintype "bidirectional"))
    )
    (net (code "82") (name "/Part3_DigCh6_N") (class "Default")
      (node (ref "U1") (pin "P3") (pinfunction "IO,_DIFFIO_L23n,_(DQ1L)/(DQ3L)/(DQ1L)_P3") (pintype "bidirectional"))
    )
    (net (code "83") (name "/Part3_DigCh6_P") (class "Default")
      (node (ref "U1") (pin "P4") (pinfunction "IO,_DIFFIO_L23p,_(DQS1L/CQ1L#,DPCLK1)/(DQS1L/CQ1L#,DPCLK1)/(DQS1L/CQ1L#,DPCLK1)_P4") (pintype "bidirectional"))
    )
    (net (code "84") (name "/Part3_DigCh7_N") (class "Default")
      (node (ref "U1") (pin "R3") (pinfunction "IO,_DIFFIO_L27n_R3") (pintype "bidirectional"))
    )
    (net (code "85") (name "/Part3_DigCh7_P") (class "Default")
      (node (ref "U1") (pin "R4") (pinfunction "IO,_DIFFIO_L27p_R4") (pintype "bidirectional"))
    )
    (net (code "86") (name "/Part3_DigCh8_N") (class "Default")
      (node (ref "U1") (pin "R6") (pinfunction "IO,_DIFFIO_L33n_R6") (pintype "bidirectional"))
    )
    (net (code "87") (name "/Part3_DigCh8_P") (class "Default")
      (node (ref "U1") (pin "T5") (pinfunction "IO,_DIFFIO_L33p,_(DM3L/BWS#3L)/(DM3L/BWS#3L)/(DM1L/BWS#1L)_T5") (pintype "bidirectional"))
    )
    (net (code "88") (name "/Part4_DigCh1_N") (class "Default")
      (node (ref "U1") (pin "M1") (pinfunction "IO,_DIFFIO_L17n,__/(DQ1L)/(DQ1L)_M1") (pintype "bidirectional"))
    )
    (net (code "89") (name "/Part4_DigCh1_P") (class "Default")
      (node (ref "U1") (pin "M2") (pinfunction "IO,_DIFFIO_L17p,_(DQ0L)/(DQ1L)/(DQ1L)_M2") (pintype "bidirectional"))
    )
    (net (code "90") (name "/Part4_DigCh2_N") (class "Default")
      (node (ref "U1") (pin "N1") (pinfunction "IO,_DIFFIO_L19n,_(DQ1L)/(DQ3L)/(DQ1L)_N1") (pintype "bidirectional"))
    )
    (net (code "91") (name "/Part4_DigCh2_P") (class "Default")
      (node (ref "U1") (pin "N2") (pinfunction "IO,_DIFFIO_L19p,_(DQ1L)/(DQ3L)/(DQ1L)_N2") (pintype "bidirectional"))
    )
    (net (code "92") (name "/Part4_DigCh3_N") (class "Default")
      (node (ref "U1") (pin "P1") (pinfunction "IO,_DIFFIO_L20n,_(DQ1L)/(DQ3L)/(DQ1L)_P1") (pintype "bidirectional"))
    )
    (net (code "93") (name "/Part4_DigCh3_P") (class "Default")
      (node (ref "U1") (pin "P2") (pinfunction "IO,_DIFFIO_L20p,_(DQ1L)/(DQ3L)/(DQ1L)_P2") (pintype "bidirectional"))
    )
    (net (code "94") (name "/Part4_DigCh4_N") (class "Default")
      (node (ref "U1") (pin "R1") (pinfunction "IO,_DIFFIO_L21n,_(DQ1L)/(DQ3L)/(DQ1L)_R1") (pintype "bidirectional"))
    )
    (net (code "95") (name "/Part4_DigCh4_P") (class "Default")
      (node (ref "U1") (pin "R2") (pinfunction "IO,_DIFFIO_L21p,_(DQ1L)/(DQ3L)/(DQ1L)_R2") (pintype "bidirectional"))
    )
    (net (code "96") (name "/Part4_DigCh5_N") (class "Default")
      (node (ref "U1") (pin "U1") (pinfunction "IO,_DIFFIO_L24n,_(DQ3L)/(DQ3L)/(DQ1L)_U1") (pintype "bidirectional"))
    )
    (net (code "97") (name "/Part4_DigCh5_P") (class "Default")
      (node (ref "U1") (pin "U2") (pinfunction "IO,_DIFFIO_L24p,_(DM1L/BWS#1L)/(DM3L/BWS#3L)/(DM1L/BWS#1L)_U2") (pintype "bidirectional"))
    )
    (net (code "98") (name "/Part4_DigCh6_N") (class "Default")
      (node (ref "U1") (pin "V1") (pinfunction "IO,_DIFFIO_L25n,_(DQ3L)/(DQ3L)/(DQ1L)_V1") (pintype "bidirectional"))
    )
    (net (code "99") (name "/Part4_DigCh6_P") (class "Default")
      (node (ref "U1") (pin "V2") (pinfunction "IO,_DIFFIO_L25p,_(DQ3L)/(DQ3L)/(DQ1L)_V2") (pintype "bidirectional"))
    )
    (net (code "100") (name "/Part4_DigCh7_N") (class "Default")
      (node (ref "U1") (pin "W1") (pinfunction "IO,_DIFFIO_L28n,_(DQ3L)/(DQ3L)/(DQ1L)_W1") (pintype "bidirectional"))
    )
    (net (code "101") (name "/Part4_DigCh7_P") (class "Default")
      (node (ref "U1") (pin "W2") (pinfunction "IO,_DIFFIO_L28p,_(DQ3L)/(DQ3L)/(DQ1L)_W2") (pintype "bidirectional"))
    )
    (net (code "102") (name "/Part4_DigCh8_N") (class "Default")
      (node (ref "U1") (pin "Y1") (pinfunction "IO,_DIFFIO_L29n,_(DQ3L)/(DQ3L)/(DQ1L)_Y1") (pintype "bidirectional"))
    )
    (net (code "103") (name "/Part4_DigCh8_P") (class "Default")
      (node (ref "U1") (pin "Y2") (pinfunction "IO,_DIFFIO_L29p,_(DQ3L)/(DQ3L)/(DQ1L)_Y2") (pintype "bidirectional"))
    )
    (net (code "104") (name "/Part5_DigCh1_N") (class "Default")
      (node (ref "U1") (pin "Y3") (pinfunction "IO,_DIFFIO_B3n,_(DQ3B)/(DQ3B)/(DQ5B)_Y3") (pintype "bidirectional"))
    )
    (net (code "105") (name "/Part5_DigCh1_P") (class "Default")
      (node (ref "U1") (pin "Y4") (pinfunction "IO,_DIFFIO_B3p_Y4") (pintype "bidirectional"))
    )
    (net (code "106") (name "/Part5_DigCh2_N") (class "Default")
      (node (ref "U1") (pin "AB5") (pinfunction "IO,_DIFFIO_B6n_AB5") (pintype "bidirectional"))
    )
    (net (code "107") (name "/Part5_DigCh2_P") (class "Default")
      (node (ref "U1") (pin "AB6") (pinfunction "IO,_DIFFIO_B6p_AB6") (pintype "bidirectional"))
    )
    (net (code "108") (name "/Part5_DigCh3_N") (class "Default")
      (node (ref "U1") (pin "AA6") (pinfunction "IO,_DIFFIO_B5n_AA6") (pintype "bidirectional"))
    )
    (net (code "109") (name "/Part5_DigCh3_P") (class "Default")
      (node (ref "U1") (pin "AA5") (pinfunction "IO,_DIFFIO_B5p,_(DQ3B)/(DQ3B)/(DQ5B)_AA5") (pintype "bidirectional"))
    )
    (net (code "110") (name "/Part5_DigCh4_N") (class "Default")
      (node (ref "U1") (pin "AB7") (pinfunction "IO,_DIFFIO_B10n,_(DQ5B)/(DQ3B)/(DQ5B)_AB7") (pintype "bidirectional"))
    )
    (net (code "111") (name "/Part5_DigCh4_P") (class "Default")
      (node (ref "U1") (pin "AA7") (pinfunction "IO,_DIFFIO_B10p,_(DM5B/BWS#5B)/(DM3B/BWS#3B)/(DM5B/BWS#5B)_AA7") (pintype "bidirectional"))
    )
    (net (code "112") (name "/Part5_DigCh5_N") (class "Default")
      (node (ref "U1") (pin "AB8") (pinfunction "IO,_DIFFIO_B17n,_(DQ5B)/(DQ3B)/(DQ5B)_AB8") (pintype "bidirectional"))
    )
    (net (code "113") (name "/Part5_DigCh5_P") (class "Default")
      (node (ref "U1") (pin "AA8") (pinfunction "IO,_DIFFIO_B17p,_(DQ5B)/(DQ3B)/(DQ5B)_AA8") (pintype "bidirectional"))
    )
    (net (code "114") (name "/Part5_DigCh6_N") (class "Default")
      (node (ref "U1") (pin "AB9") (pinfunction "IO,_DIFFIO_B18n,_(DQS5B/CQ5B#,DPCLK3)/(DQS5B/CQ5B#,DPCLK3)/(DQS5B/CQ5B#,DPCLK3)_AB9") (pintype "bidirectional"))
    )
    (net (code "115") (name "/Part5_DigCh6_P") (class "Default")
      (node (ref "U1") (pin "AA9") (pinfunction "IO,_DIFFIO_B18p,_(DQ5B)/(DQ3B)/(DQ5B)_AA9") (pintype "bidirectional"))
    )
    (net (code "116") (name "/Part5_DigCh7_N") (class "Default")
      (node (ref "U1") (pin "Y10") (pinfunction "IO,_DIFFIO_B20n,_(DQ5B)/(DQ3B)/(DQ5B)_Y10") (pintype "bidirectional"))
    )
    (net (code "117") (name "/Part5_DigCh7_P") (class "Default")
      (node (ref "U1") (pin "W10") (pinfunction "IO,_DIFFIO_B20p,_(DQ5B)/(DQ3B)/(DQ5B)_W10") (pintype "bidirectional"))
    )
    (net (code "118") (name "/Part5_DigCh8_N") (class "Default")
      (node (ref "U1") (pin "AB10") (pinfunction "IO,_DIFFIO_B21n,__/(DQ5B)/(DQ5B)_AB10") (pintype "bidirectional"))
    )
    (net (code "119") (name "/Part5_DigCh8_P") (class "Default")
      (node (ref "U1") (pin "AA10") (pinfunction "IO,_DIFFIO_B21p,_(DM4B)/(DM5B/BWS#5B)/(DM5B/BWS#5B)_AA10") (pintype "bidirectional"))
    )
    (net (code "120") (name "/Pre Beam time_N") (class "Default")
      (node (ref "U1") (pin "D22") (pinfunction "IO,_DIFFIO_R7n,_(DM2R)/(DM1R/BWS#1R)/(DM1R/BWS#1R)_D22") (pintype "bidirectional"))
    )
    (net (code "121") (name "/Pre Beam time_P") (class "Default")
      (node (ref "U1") (pin "D21") (pinfunction "IO,_DIFFIO_R7p,__/(DQ1R)/(DQ1R)_D21") (pintype "bidirectional"))
    )
    (net (code "122") (name "/SW_FCT-CLK") (class "Default")
      (node (ref "U1") (pin "A14") (pinfunction "IO,_DIFFIO_T25n,_(PADD9),_(DQ4T)/(DQ5T)/(DQ5T)_A14") (pintype "bidirectional"))
      (node (ref "UG2") (pin "8") (pinfunction "CONTROL_8") (pintype "input"))
    )
    (net (code "123") (name "/SW_Quartz") (class "Default")
      (node (ref "U1") (pin "B13") (pinfunction "IO,_DIFFIO_T24p,_(PADD12),_(DQS4T/CQ5T,DPCLK9)/(DQS4T/CQ5T,DPCLK9)/(DQS4T/CQ5T,DPCLK9)_B13") (pintype "bidirectional"))
      (node (ref "UG2") (pin "1") (pinfunction "CONTROL_1") (pintype "input"))
    )
    (net (code "124") (name "/Signal Window_N") (class "Default")
      (node (ref "U1") (pin "J22") (pinfunction "IO,_DIFFIO_R15n,_(DQS0R/CQ1R,DPCLK7)/(DQS0R/CQ1R,DPCLK7)/(DQS0R/CQ1R,DPCLK7)_J22") (pintype "bidirectional"))
    )
    (net (code "125") (name "/Signal Window_P") (class "Default")
      (node (ref "U1") (pin "J21") (pinfunction "IO,_DIFFIO_R15p,_(DM0R)/(DM1R/BWS#1R)/(DM1R/BWS#1R)_J21") (pintype "bidirectional"))
    )
    (net (code "126") (name "/Status IN 1_N") (class "Default")
      (node (ref "U1") (pin "A16") (pinfunction "IO,_DIFFIO_T30n,_(DM2T)/(DM5T/BWS#5T)/(DM5T/BWS#5T)_A16") (pintype "bidirectional"))
    )
    (net (code "127") (name "/Status IN 1_P") (class "Default")
      (node (ref "U1") (pin "B16") (pinfunction "IO,_DIFFIO_T30p,_(DQ4T)/(DQ5T)/(DQ5T)_B16") (pintype "bidirectional"))
    )
    (net (code "128") (name "/Status IN 2_N") (class "Default")
      (node (ref "U1") (pin "F15") (pinfunction "IO,_DIFFIO_T41n,_(DQ2T)/(DQ5T)/(DQ5T)_F15") (pintype "bidirectional"))
    )
    (net (code "129") (name "/Status IN 2_P") (class "Default")
      (node (ref "U1") (pin "G16") (pinfunction "IO,_DIFFIO_T41p_G16") (pintype "bidirectional"))
    )
    (net (code "130") (name "/Status IN 3_N") (class "Default")
      (node (ref "U1") (pin "D15") (pinfunction "IO,_DIFFIO_T33n_D15") (pintype "bidirectional"))
    )
    (net (code "131") (name "/Status IN 3_P") (class "Default")
      (node (ref "U1") (pin "E15") (pinfunction "IO,_DIFFIO_T33p,_(DQ2T)/(DQ5T)/(DQ5T)_E15") (pintype "bidirectional"))
    )
    (net (code "132") (name "/Status IN 4_N") (class "Default")
      (node (ref "U1") (pin "F16") (pinfunction "IO,_DIFFIO_T42n_F16") (pintype "bidirectional"))
    )
    (net (code "133") (name "/Status IN 4_P") (class "Default")
      (node (ref "U1") (pin "E16") (pinfunction "IO,_DIFFIO_T42p,_(DQ2T)/(DQ5T)/(DQ5T)_E16") (pintype "bidirectional"))
    )
    (net (code "134") (name "/TCK") (class "Default")
      (node (ref "R8") (pin "2") (pinfunction "2_2") (pintype "passive"))
      (node (ref "U1") (pin "L2") (pinfunction "TCK_L2") (pintype "input"))
    )
    (net (code "135") (name "/TDI") (class "Default")
      (node (ref "R6") (pin "2") (pinfunction "2_2") (pintype "passive"))
      (node (ref "U1") (pin "L5") (pinfunction "TDI_L5") (pintype "input"))
    )
    (net (code "136") (name "/TMS") (class "Default")
      (node (ref "R7") (pin "2") (pinfunction "2_2") (pintype "passive"))
      (node (ref "U1") (pin "L1") (pinfunction "TMS_L1") (pintype "input"))
    )
    (net (code "137") (name "/Test0") (class "Default")
      (node (ref "U1") (pin "W13") (pinfunction "IO,_DIFFIO_B26p,_(DQ4B)/(DQ5B)/(DQ5B)_W13") (pintype "bidirectional"))
    )
    (net (code "138") (name "/Test1") (class "Default")
      (node (ref "U1") (pin "W14") (pinfunction "IO,_DIFFIO_B31n_W14") (pintype "bidirectional"))
    )
    (net (code "139") (name "/Test2") (class "Default")
      (node (ref "U1") (pin "W15") (pinfunction "IO,_DIFFIO_B35p,_(DQ2B)/(DQ5B)/(DQ5B)_W15") (pintype "bidirectional"))
    )
    (net (code "140") (name "/Test3") (class "Default")
      (node (ref "U1") (pin "Y13") (pinfunction "IO,_DIFFIO_B26n,_(DQS4B/CQ5B,DPCLK4)/(DQS4B/CQ5B,DPCLK4)/(DQS4B/CQ5B,DPCLK4)_Y13") (pintype "bidirectional"))
    )
    (net (code "141") (name "/Test4") (class "Default")
      (node (ref "U1") (pin "Y14") (pinfunction "IO,_DIFFIO_B29p_Y14") (pintype "bidirectional"))
    )
    (net (code "142") (name "/Test5") (class "Default")
      (node (ref "U1") (pin "Y15") (pinfunction "IO,_DIFFIO_B29n_Y15") (pintype "bidirectional"))
    )
    (net (code "143") (name "/Trig_Light") (class "Default")
      (node (ref "U1") (pin "C7") (pinfunction "IO,_DIFFIO_T13p,_(DATA13),_(DM5T/BWS#5T)/(DM3T/BWS#3T)/(DM5T/BWS#5T)_C7") (pintype "bidirectional"))
    )
    (net (code "144") (name "/Trigger data1_N") (class "Default")
      (node (ref "U1") (pin "N22") (pinfunction "IO,_DIFFIO_R20n,_(DEV_OE)_N22") (pintype "bidirectional"))
    )
    (net (code "145") (name "/Trigger data1_P") (class "Default")
      (node (ref "U1") (pin "N21") (pinfunction "IO,_DIFFIO_R20p,_(DEV_CLRn)_N21") (pintype "bidirectional"))
    )
    (net (code "146") (name "/Trigger data2_N") (class "Default")
      (node (ref "U1") (pin "U22") (pinfunction "IO,_DIFFIO_R27n,_(DQ3R)/(DQ3R)/(DQ1R)_U22") (pintype "bidirectional"))
    )
    (net (code "147") (name "/Trigger data2_P") (class "Default")
      (node (ref "U1") (pin "U21") (pinfunction "IO,_DIFFIO_R27p,_(DQ3R)/(DQ3R)/(DQ1R)_U21") (pintype "bidirectional"))
    )
    (net (code "148") (name "/Trigger data3_N") (class "Default")
      (node (ref "U1") (pin "R18") (pinfunction "IO,_DIFFIO_R26n_R18") (pintype "bidirectional"))
    )
    (net (code "149") (name "/Trigger data3_P") (class "Default")
      (node (ref "U1") (pin "R19") (pinfunction "IO,_DIFFIO_R26p,_(DM1R/BWS#1R)/(DM3R/BWS#3R)/(DM1R/BWS#1R)_R19") (pintype "bidirectional"))
    )
    (net (code "150") (name "/Trigger data4_N") (class "Default")
      (node (ref "U1") (pin "M20") (pinfunction "IO,_DIFFIO_R18n,_(DQ1R)/(DQ3R)/(DQ1R)_M20") (pintype "bidirectional"))
    )
    (net (code "151") (name "/Trigger data4_P") (class "Default")
      (node (ref "U1") (pin "M19") (pinfunction "IO,_DIFFIO_R18p,_(DQ1R)/(DQ3R)/(DQ1R)_M19") (pintype "bidirectional"))
    )
    (net (code "152") (name "/Trigger data5_N") (class "Default")
      (node (ref "U1") (pin "R22") (pinfunction "IO,_DIFFIO_R24n,_(DQ1R)/(DQ3R)/(DQ1R)_R22") (pintype "bidirectional"))
    )
    (net (code "153") (name "/Trigger data5_P") (class "Default")
      (node (ref "U1") (pin "R21") (pinfunction "IO,_DIFFIO_R24p,_(DQ1R)/(DQ3R)/(DQ1R)_R21") (pintype "bidirectional"))
    )
    (net (code "154") (name "/Trigger data6_N") (class "Default")
      (node (ref "U1") (pin "U20") (pinfunction "IO,_DIFFIO_R34n,_(DQ3R)/(DQ3R)/(DQ1R)_U20") (pintype "bidirectional"))
    )
    (net (code "155") (name "/Trigger data6_P") (class "Default")
      (node (ref "U1") (pin "U19") (pinfunction "IO,_DIFFIO_R34p_U19") (pintype "bidirectional"))
    )
    (net (code "156") (name "/Trigger data7_N") (class "Default")
      (node (ref "U1") (pin "W22") (pinfunction "IO,_DIFFIO_R32n,_(DQ3R)/(DQ3R)/(DQ1R)_W22") (pintype "bidirectional"))
    )
    (net (code "157") (name "/Trigger data7_P") (class "Default")
      (node (ref "U1") (pin "W21") (pinfunction "IO,_DIFFIO_R32p,_(DQ3R)/(DQ3R)/(DQ1R)_W21") (pintype "bidirectional"))
    )
    (net (code "158") (name "/Trigger data8_N") (class "Default")
      (node (ref "U1") (pin "V22") (pinfunction "IO,_DIFFIO_R29n,_(DQ3R)/(DQ3R)/(DQ1R)_V22") (pintype "bidirectional"))
    )
    (net (code "159") (name "/Trigger data8_P") (class "Default")
      (node (ref "U1") (pin "V21") (pinfunction "IO,_DIFFIO_R29p,_(DQ3R)/(DQ3R)/(DQ1R)_V21") (pintype "bidirectional"))
    )
    (net (code "160") (name "/Trigger data9_N") (class "Default")
      (node (ref "U1") (pin "C22") (pinfunction "IO,_DIFFIO_R4n,_(DQ2R)/(DQ1R)/(DQ1R)_C22") (pintype "bidirectional"))
    )
    (net (code "161") (name "/Trigger data9_P") (class "Default")
      (node (ref "U1") (pin "C21") (pinfunction "IO,_DIFFIO_R4p,_(DQ2R)/(DQ1R)/(DQ1R)_C21") (pintype "bidirectional"))
    )
    (net (code "162") (name "/Trigger data10_N") (class "Default")
      (node (ref "U1") (pin "C20") (pinfunction "IO,_DIFFIO_R2n,_(PADD20),_(DQS2R/CQ3R,CDPCLK5)/(DQS2R/CQ3R,CDPCLK5)/(DQS2R/CQ3R,CDPCLK5)_C20") (pintype "bidirectional"))
    )
    (net (code "163") (name "/Trigger data10_P") (class "Default")
      (node (ref "U1") (pin "D20") (pinfunction "IO,_DIFFIO_R2p_D20") (pintype "bidirectional"))
    )
    (net (code "164") (name "/Trigger data11_N") (class "Default")
      (node (ref "U1") (pin "F22") (pinfunction "IO,_DIFFIO_R11n,_(DQ0R)/(DQ1R)/(DQ1R)_F22") (pintype "bidirectional"))
    )
    (net (code "165") (name "/Trigger data11_P") (class "Default")
      (node (ref "U1") (pin "F21") (pinfunction "IO,_DIFFIO_R11p,_(DQ0R)/(DQ1R)/(DQ1R)_F21") (pintype "bidirectional"))
    )
    (net (code "166") (name "/Trigger data12_N") (class "Default")
      (node (ref "U1") (pin "H22") (pinfunction "IO,_DIFFIO_R14n,_(DQ0R)/(DQ1R)/(DQ1R)_H22") (pintype "bidirectional"))
    )
    (net (code "167") (name "/Trigger data12_P") (class "Default")
      (node (ref "U1") (pin "H21") (pinfunction "IO,_DIFFIO_R14p,_(DQ0R)/(DQ1R)/(DQ1R)_H21") (pintype "bidirectional"))
    )
    (net (code "168") (name "/Trigger data13_N") (class "Default")
      (node (ref "U1") (pin "K17") (pinfunction "IO,_DIFFIO_R13n_K17") (pintype "bidirectional"))
    )
    (net (code "169") (name "/Trigger data13_P") (class "Default")
      (node (ref "U1") (pin "K18") (pinfunction "IO,_DIFFIO_R13p,_(DQ0R)/(DQ1R)/(DQ1R)_K18") (pintype "bidirectional"))
    )
    (net (code "170") (name "/Trigger data14_N") (class "Default")
      (node (ref "U1") (pin "M22") (pinfunction "IO,_DIFFIO_R19n,_(DQ1R)/(DQ3R)/(DQ1R)_M22") (pintype "bidirectional"))
    )
    (net (code "171") (name "/Trigger data14_P") (class "Default")
      (node (ref "U1") (pin "M21") (pinfunction "IO,_DIFFIO_R19p,_(DQ1R)/(DQ3R)/(DQ1R)_M21") (pintype "bidirectional"))
    )
    (net (code "172") (name "/Trigger data15_N") (class "Default")
      (node (ref "U1") (pin "P22") (pinfunction "IO,_DIFFIO_R23n,_(DQ1R)/(DQ3R)/(DQ1R)_P22") (pintype "bidirectional"))
    )
    (net (code "173") (name "/Trigger data15_P") (class "Default")
      (node (ref "U1") (pin "P21") (pinfunction "IO,_DIFFIO_R23p,_(DQ1R)/(DQ3R)/(DQ1R)_P21") (pintype "bidirectional"))
    )
    (net (code "174") (name "/Trigger data16_N") (class "Default")
      (node (ref "U1") (pin "N20") (pinfunction "IO,_DIFFIO_R22n,_(DQ1R)/(DQ3R)/(DQ1R)_N20") (pintype "bidirectional"))
    )
    (net (code "175") (name "/Trigger data16_P") (class "Default")
      (node (ref "U1") (pin "N19") (pinfunction "IO,_DIFFIO_R22p_N19") (pintype "bidirectional"))
    )
    (net (code "176") (name "/Trigger data17_N") (class "Default")
      (node (ref "U1") (pin "H20") (pinfunction "IO,_DIFFIO_R9n,_(DQ0R)/(DQ1R)/(DQ1R)_H20") (pintype "bidirectional"))
    )
    (net (code "177") (name "/Trigger data17_P") (class "Default")
      (node (ref "U1") (pin "H19") (pinfunction "IO,_DIFFIO_R9p,_(DQ0R)/(DQ1R)/(DQ1R)_H19") (pintype "bidirectional"))
    )
    (net (code "178") (name "/Trigger data18_N") (class "Default")
      (node (ref "U1") (pin "F17") (pinfunction "IO,_DIFFIO_R1n,_(DQ2R)/(DQ1R)/(DQ1R)_F17") (pintype "bidirectional"))
    )
    (net (code "179") (name "/Trigger data18_P") (class "Default")
      (node (ref "U1") (pin "G17") (pinfunction "IO,_DIFFIO_R1p_G17") (pintype "bidirectional"))
    )
    (net (code "180") (name "/Trigger data19_N") (class "Default")
      (node (ref "U1") (pin "G18") (pinfunction "IO,_DIFFIO_R5n,_(PADD23),_(DQ2R)/(DQ1R)/(DQ1R)_G18") (pintype "bidirectional"))
    )
    (net (code "181") (name "/Trigger data19_P") (class "Default")
      (node (ref "U1") (pin "H17") (pinfunction "IO,_DIFFIO_R5p_H17") (pintype "bidirectional"))
    )
    (net (code "182") (name "/Trigger data20_N") (class "Default")
      (node (ref "U1") (pin "F20") (pinfunction "IO,_DIFFIO_R6n,_(nAVD),_(DQ2R)/(DQ1R)/(DQ1R)_F20") (pintype "bidirectional"))
    )
    (net (code "183") (name "/Trigger data20_P") (class "Default")
      (node (ref "U1") (pin "F19") (pinfunction "IO,_DIFFIO_R6p,_(DQ2R)/(DQ1R)/(DQ1R)_F19") (pintype "bidirectional"))
    )
    (net (code "184") (name "/Trigger data21_N") (class "Default")
      (node (ref "U1") (pin "N17") (pinfunction "IO,_DIFFIO_R21n_N17") (pintype "bidirectional"))
    )
    (net (code "185") (name "/Trigger data21_P") (class "Default")
      (node (ref "U1") (pin "N18") (pinfunction "IO,_DIFFIO_R21p,_(DQS1R/CQ1R#,DPCLK6)/(DQS1R/CQ1R#,DPCLK6)/(DQS1R/CQ1R#,DPCLK6)_N18") (pintype "bidirectional"))
    )
    (net (code "186") (name "/Trigger data22_N") (class "Default")
      (node (ref "U1") (pin "J20") (pinfunction "IO,_DIFFIO_R10n_J20") (pintype "bidirectional"))
    )
    (net (code "187") (name "/Trigger data22_P") (class "Default")
      (node (ref "U1") (pin "J19") (pinfunction "IO,_DIFFIO_R10p_J19") (pintype "bidirectional"))
    )
    (net (code "188") (name "/Trigger data23_N") (class "Default")
      (node (ref "U1") (pin "T20") (pinfunction "IO,_DIFFIO_R31n_T20") (pintype "bidirectional"))
    )
    (net (code "189") (name "/Trigger data23_P") (class "Default")
      (node (ref "U1") (pin "T19") (pinfunction "IO,_DIFFIO_R31p_T19") (pintype "bidirectional"))
    )
    (net (code "190") (name "/Trigger data24_N") (class "Default")
      (node (ref "U1") (pin "Y22") (pinfunction "IO,_DIFFIO_R35n,_(DQ3R)/(DQ3R)/(DQ1R)_Y22") (pintype "bidirectional"))
    )
    (net (code "191") (name "/Trigger data24_P") (class "Default")
      (node (ref "U1") (pin "Y21") (pinfunction "IO,_DIFFIO_R35p_Y21") (pintype "bidirectional"))
    )
    (net (code "272") (name "/Trigger_N") (class "Default")
      (node (ref "U1") (pin "A17") (pinfunction "IO,_DIFFIO_T31n,_(PADD1),_(DQ2T)/(DQ5T)/(DQ5T)_A17") (pintype "bidirectional"))
    )
    (net (code "273") (name "/Trigger_P") (class "Default")
      (node (ref "U1") (pin "B17") (pinfunction "IO,_DIFFIO_T31p,_(PADD2),__/(DQ5T)/(DQ5T)_B17") (pintype "bidirectional"))
    )
    (net (code "274") (name "/nCONFIG") (class "Default")
      (node (ref "R3") (pin "2") (pinfunction "2_2") (pintype "passive"))
      (node (ref "U1") (pin "K5") (pinfunction "nCONFIG_K5") (pintype "input"))
      (node (ref "U3") (pin "5") (pinfunction "5_5") (pintype "bidirectional"))
    )
    (net (code "275") (name "/nSTATUS") (class "Default")
      (node (ref "R5") (pin "2") (pinfunction "2_2") (pintype "passive"))
      (node (ref "U1") (pin "K6") (pinfunction "nSTATUS_K6") (pintype "bidirectional"))
    )
    (net (code "276") (name "GND") (class "Default")
      (node (ref "C10") (pin "1") (pinfunction "1_1") (pintype "passive"))
      (node (ref "C11") (pin "1") (pinfunction "1_1") (pintype "passive"))
      (node (ref "C12") (pin "1") (pinfunction "1_1") (pintype "passive"))
      (node (ref "C13") (pin "1") (pinfunction "1_1") (pintype "passive"))
      (node (ref "C14") (pin "1") (pinfunction "1_1") (pintype "passive"))
      (node (ref "C15") (pin "1") (pinfunction "1_1") (pintype "passive"))
      (node (ref "C16") (pin "1") (pinfunction "1_1") (pintype "passive"))
      (node (ref "C17") (pin "1") (pinfunction "1_1") (pintype "passive"))
      (node (ref "C18") (pin "2") (pinfunction "2_2") (pintype "passive"))
      (node (ref "C19") (pin "1") (pinfunction "1_1") (pintype "passive"))
      (node (ref "C20") (pin "1") (pinfunction "1_1") (pintype "passive"))
      (node (ref "C21") (pin "1") (pinfunction "1_1") (pintype "passive"))
      (node (ref "C22") (pin "1") (pinfunction "1_1") (pintype "passive"))
      (node (ref "C23") (pin "1") (pinfunction "1_1") (pintype "passive"))
      (node (ref "C24") (pin "1") (pinfunction "1_1") (pintype "passive"))
      (node (ref "C25") (pin "1") (pinfunction "1_1") (pintype "passive"))
      (node (ref "C26") (pin "1") (pinfunction "1_1") (pintype "passive"))
      (node (ref "C4") (pin "1") (pinfunction "1_1") (pintype "passive"))
      (node (ref "C5") (pin "1") (pinfunction "1_1") (pintype "passive"))
      (node (ref "C6") (pin "1") (pinfunction "1_1") (pintype "passive"))
      (node (ref "C7") (pin "1") (pinfunction "1_1") (pintype "passive"))
      (node (ref "C8") (pin "1") (pinfunction "1_1") (pintype "passive"))
      (node (ref "C9") (pin "1") (pinfunction "1_1") (pintype "passive"))
      (node (ref "CL1") (pin "2") (pinfunction "2_2") (pintype "passive"))
      (node (ref "Cgen1") (pin "1") (pinfunction "1_1") (pintype "passive"))
      (node (ref "ExtReset") (pin "2") (pinfunction "2_2") (pintype "passive"))
      (node (ref "R8") (pin "1") (pinfunction "1_1") (pintype "passive"))
      (node (ref "R9") (pin "2") (pinfunction "2_2") (pintype "passive"))
      (node (ref "RL4") (pin "2") (pinfunction "2_2") (pintype "passive"))
      (node (ref "RL5") (pin "2") (pinfunction "2_2") (pintype "passive"))
      (node (ref "U1") (pin "A1") (pinfunction "GND_A1") (pintype "power_in"))
      (node (ref "U1") (pin "A11") (pinfunction "CLK10,_DIFFCLK_4n_A11") (pintype "input"))
      (node (ref "U1") (pin "A12") (pinfunction "CLK8,_DIFFCLK_5n_A12") (pintype "input"))
      (node (ref "U1") (pin "A22") (pinfunction "GND_A22") (pintype "power_in"))
      (node (ref "U1") (pin "AA11") (pinfunction "CLK15,_DIFFCLK_6p_AA11") (pintype "input"))
      (node (ref "U1") (pin "AA12") (pinfunction "CLK13,_DIFFCLK_7p_AA12") (pintype "input"))
      (node (ref "U1") (pin "AA2") (pinfunction "GND_AA2") (pintype "power_in"))
      (node (ref "U1") (pin "AA22") (pinfunction "GND_AA22") (pintype "power_in"))
      (node (ref "U1") (pin "AB1") (pinfunction "GND_AB1") (pintype "power_in"))
      (node (ref "U1") (pin "AB11") (pinfunction "CLK14,_DIFFCLK_6n_AB11") (pintype "input"))
      (node (ref "U1") (pin "AB12") (pinfunction "CLK12,_DIFFCLK_7n_AB12") (pintype "input"))
      (node (ref "U1") (pin "AB22") (pinfunction "GND_AB22") (pintype "power_in"))
      (node (ref "U1") (pin "B11") (pinfunction "CLK11,_DIFFCLK_4p_B11") (pintype "input"))
      (node (ref "U1") (pin "B12") (pinfunction "CLK9,_DIFFCLK_5p_B12") (pintype "input"))
      (node (ref "U1") (pin "C11") (pinfunction "GND_C11") (pintype "power_in"))
      (node (ref "U1") (pin "C12") (pinfunction "GND_C12") (pintype "power_in"))
      (node (ref "U1") (pin "C14") (pinfunction "GND_C14") (pintype "power_in"))
      (node (ref "U1") (pin "C16") (pinfunction "GND_C16") (pintype "power_in"))
      (node (ref "U1") (pin "C5") (pinfunction "GND_C5") (pintype "power_in"))
      (node (ref "U1") (pin "C9") (pinfunction "GND_C9") (pintype "power_in"))
      (node (ref "U1") (pin "D3") (pinfunction "GND_D3") (pintype "power_in"))
      (node (ref "U1") (pin "E18") (pinfunction "GNDA2_E18") (pintype "power_in"))
      (node (ref "U1") (pin "E20") (pinfunction "GND_E20") (pintype "power_in"))
      (node (ref "U1") (pin "F12") (pinfunction "GND_F12") (pintype "power_in"))
      (node (ref "U1") (pin "F3") (pinfunction "GND_F3") (pintype "power_in"))
      (node (ref "U1") (pin "F5") (pinfunction "GNDA3_F5") (pintype "power_in"))
      (node (ref "U1") (pin "G2") (pinfunction "GND_G2") (pintype "power_in"))
      (node (ref "U1") (pin "G20") (pinfunction "GND_G20") (pintype "power_in"))
      (node (ref "U1") (pin "G21") (pinfunction "CLK4,_DIFFCLK_2p_G21") (pintype "input"))
      (node (ref "U1") (pin "G22") (pinfunction "CLK5,_DIFFCLK_2n_G22") (pintype "input"))
      (node (ref "U1") (pin "H10") (pinfunction "GND_H10") (pintype "power_in"))
      (node (ref "U1") (pin "H12") (pinfunction "GND_H12") (pintype "power_in"))
      (node (ref "U1") (pin "H13") (pinfunction "GND_H13") (pintype "power_in"))
      (node (ref "U1") (pin "H14") (pinfunction "GND_H14") (pintype "power_in"))
      (node (ref "U1") (pin "H8") (pinfunction "GND_H8") (pintype "power_in"))
      (node (ref "U1") (pin "J15") (pinfunction "GND_J15") (pintype "power_in"))
      (node (ref "U1") (pin "J9") (pinfunction "GND_J9") (pintype "power_in"))
      (node (ref "U1") (pin "K10") (pinfunction "GND_K10") (pintype "power_in"))
      (node (ref "U1") (pin "K11") (pinfunction "GND_K11") (pintype "power_in"))
      (node (ref "U1") (pin "K12") (pinfunction "GND_K12") (pintype "power_in"))
      (node (ref "U1") (pin "K13") (pinfunction "GND_K13") (pintype "power_in"))
      (node (ref "U1") (pin "K16") (pinfunction "GND_K16") (pintype "power_in"))
      (node (ref "U1") (pin "K20") (pinfunction "MSEL3_K20") (pintype "input"))
      (node (ref "U1") (pin "K3") (pinfunction "GND_K3") (pintype "power_in"))
      (node (ref "U1") (pin "L10") (pinfunction "GND_L10") (pintype "power_in"))
      (node (ref "U1") (pin "L11") (pinfunction "GND_L11") (pintype "power_in"))
      (node (ref "U1") (pin "L12") (pinfunction "GND_L12") (pintype "power_in"))
      (node (ref "U1") (pin "L13") (pinfunction "GND_L13") (pintype "power_in"))
      (node (ref "U1") (pin "L15") (pinfunction "GND_L15") (pintype "power_in"))
      (node (ref "U1") (pin "L17") (pinfunction "MSEL2_L17") (pintype "input"))
      (node (ref "U1") (pin "L20") (pinfunction "GND_L20") (pintype "power_in"))
      (node (ref "U1") (pin "L8") (pinfunction "GND_L8") (pintype "power_in"))
      (node (ref "U1") (pin "M10") (pinfunction "GND_M10") (pintype "power_in"))
      (node (ref "U1") (pin "M11") (pinfunction "GND_M11") (pintype "power_in"))
      (node (ref "U1") (pin "M12") (pinfunction "GND_M12") (pintype "power_in"))
      (node (ref "U1") (pin "M13") (pinfunction "GND_M13") (pintype "power_in"))
      (node (ref "U1") (pin "M17") (pinfunction "MSEL0_M17") (pintype "input"))
      (node (ref "U1") (pin "M7") (pinfunction "GND_M7") (pintype "power_in"))
      (node (ref "U1") (pin "N10") (pinfunction "GND_N10") (pintype "power_in"))
      (node (ref "U1") (pin "N11") (pinfunction "GND_N11") (pintype "power_in"))
      (node (ref "U1") (pin "N12") (pinfunction "GND_N12") (pintype "power_in"))
      (node (ref "U1") (pin "N13") (pinfunction "GND_N13") (pintype "power_in"))
      (node (ref "U1") (pin "N15") (pinfunction "GND_N15") (pintype "power_in"))
      (node (ref "U1") (pin "N3") (pinfunction "GND_N3") (pintype "power_in"))
      (node (ref "U1") (pin "N8") (pinfunction "GND_N8") (pintype "power_in"))
      (node (ref "U1") (pin "P16") (pinfunction "GND_P16") (pintype "power_in"))
      (node (ref "U1") (pin "P19") (pinfunction "GND_P19") (pintype "power_in"))
      (node (ref "U1") (pin "P8") (pinfunction "GND_P8") (pintype "power_in"))
      (node (ref "U1") (pin "R11") (pinfunction "GND_R11") (pintype "power_in"))
      (node (ref "U1") (pin "R13") (pinfunction "GND_R13") (pintype "power_in"))
      (node (ref "U1") (pin "R7") (pinfunction "GND_R7") (pintype "power_in"))
      (node (ref "U1") (pin "R9") (pinfunction "GND_R9") (pintype "power_in"))
      (node (ref "U1") (pin "T1") (pinfunction "CLK3,_DIFFCLK_1n_T1") (pintype "input"))
      (node (ref "U1") (pin "T12") (pinfunction "GND_T12") (pintype "power_in"))
      (node (ref "U1") (pin "T2") (pinfunction "CLK2,_DIFFCLK_1p_T2") (pintype "input"))
      (node (ref "U1") (pin "T21") (pinfunction "CLK6,_DIFFCLK_3p_T21") (pintype "input"))
      (node (ref "U1") (pin "T22") (pinfunction "CLK7,_DIFFCLK_3n_T22") (pintype "input"))
      (node (ref "U1") (pin "T8") (pinfunction "GND_T8") (pintype "power_in"))
      (node (ref "U1") (pin "U3") (pinfunction "GND_U3") (pintype "power_in"))
      (node (ref "U1") (pin "U5") (pinfunction "GNDA1_U5") (pintype "power_in"))
      (node (ref "U1") (pin "V18") (pinfunction "GNDA4_V18") (pintype "power_in"))
      (node (ref "U1") (pin "V20") (pinfunction "GND_V20") (pintype "power_in"))
      (node (ref "U1") (pin "W3") (pinfunction "GND_W3") (pintype "power_in"))
      (node (ref "U1") (pin "Y11") (pinfunction "GND_Y11") (pintype "power_in"))
      (node (ref "U1") (pin "Y12") (pinfunction "GND_Y12") (pintype "power_in"))
      (node (ref "U1") (pin "Y16") (pinfunction "GND_Y16") (pintype "power_in"))
      (node (ref "U1") (pin "Y18") (pinfunction "GND_Y18") (pintype "power_in"))
      (node (ref "U1") (pin "Y20") (pinfunction "GND_Y20") (pintype "power_in"))
      (node (ref "U1") (pin "Y5") (pinfunction "GND_Y5") (pintype "power_in"))
      (node (ref "U1") (pin "Y9") (pinfunction "GND_Y9") (pintype "power_in"))
      (node (ref "U2") (pin "4") (pinfunction "GND_4") (pintype "power_in"))
      (node (ref "U3") (pin "10") (pinfunction "10_10") (pintype "bidirectional"))
      (node (ref "U3") (pin "2") (pinfunction "2_2") (pintype "bidirectional"))
      (node (ref "UG1") (pin "2") (pinfunction "Gnd_2") (pintype "power_in"))
      (node (ref "UG2") (pin "5") (pinfunction "GND_5") (pintype "passive"))
      (node (ref "UL1") (pin "12") (pinfunction "WIRE-_12") (pintype "bidirectional"))
      (node (ref "UL1") (pin "3") (pinfunction "TE_3") (pintype "input"))
      (node (ref "UL1") (pin "4") (pinfunction "RE_4") (pintype "input"))
    )
    (net (code "277") (name "Net-(RL1-Pad1)") (class "Default")
      (node (ref "RL1") (pin "1") (pinfunction "1_1") (pintype "passive"))
      (node (ref "RL2") (pin "1") (pinfunction "1_1") (pintype "passive"))
      (node (ref "RL3") (pin "1") (pinfunction "1_1") (pintype "passive"))
      (node (ref "RL4") (pin "1") (pinfunction "1_1") (pintype "passive"))
    )
    (net (code "278") (name "unconnected-(U1A-IO,_DIFFIO_L3n,_(DQ2L){slash}(DQ1L){slash}(DQ1L)-PadE3)") (class "Default")
      (node (ref "U1") (pin "E3") (pinfunction "IO,_DIFFIO_L3n,_(DQ2L)/(DQ1L)/(DQ1L)_E3") (pintype "bidirectional"))
    )
    (net (code "279") (name "unconnected-(U1A-IO,_DIFFIO_L3p,_(nRESET),_(DQ2L){slash}(DQ1L){slash}(DQ1L)-PadE4)") (class "Default")
      (node (ref "U1") (pin "E4") (pinfunction "IO,_DIFFIO_L3p,_(nRESET),_(DQ2L)/(DQ1L)/(DQ1L)_E4") (pintype "bidirectional"))
    )
    (net (code "280") (name "unconnected-(U1A-IO,_DIFFIO_L5p,_(DQ2L){slash}(DQ1L){slash}(DQ1L)-PadD2)") (class "Default")
      (node (ref "U1") (pin "D2") (pinfunction "IO,_DIFFIO_L5p,_(DQ2L)/(DQ1L)/(DQ1L)_D2") (pintype "bidirectional"))
    )
    (net (code "281") (name "unconnected-(U1A-IO,_DIFFIO_L8n,__{slash}(DQ1L){slash}(DQ1L)-PadE1)") (class "Default")
      (node (ref "U1") (pin "E1") (pinfunction "IO,_DIFFIO_L8n,__/(DQ1L)/(DQ1L)_E1") (pintype "bidirectional"))
    )
    (net (code "282") (name "unconnected-(U1A-IO,_DIFFIO_L12p,_(DQS0L{slash}CQ1L,DPCLK0){slash}(DQS0L{slash}CQ1L,DPCLK0){slash}(DQS0L{slash}CQ1L,DPCLK0)-PadJ4)") (class "Default")
      (node (ref "U1") (pin "J4") (pinfunction "IO,_DIFFIO_L12p,_(DQS0L/CQ1L,DPCLK0)/(DQS0L/CQ1L,DPCLK0)/(DQS0L/CQ1L,DPCLK0)_J4") (pintype "bidirectional"))
    )
    (net (code "283") (name "unconnected-(U1A-IO,_DIFFIO_L14n-PadJ3)") (class "Default")
      (node (ref "U1") (pin "J3") (pinfunction "IO,_DIFFIO_L14n_J3") (pintype "bidirectional"))
    )
    (net (code "284") (name "unconnected-(U1A-IO,_VREFB1N0-PadG5)") (class "Default")
      (node (ref "U1") (pin "G5") (pinfunction "IO,_VREFB1N0_G5") (pintype "bidirectional"))
    )
    (net (code "285") (name "unconnected-(U1A-IO,_VREFB1N1-PadH5)") (class "Default")
      (node (ref "U1") (pin "H5") (pinfunction "IO,_VREFB1N1_H5") (pintype "bidirectional"))
    )
    (net (code "286") (name "unconnected-(U1A-IO-PadH7)") (class "Default")
      (node (ref "U1") (pin "H7") (pinfunction "IO_H7") (pintype "bidirectional"))
    )
    (net (code "287") (name "unconnected-(U1A-IO-PadJ5)") (class "Default")
      (node (ref "U1") (pin "J5") (pinfunction "IO_J5") (pintype "bidirectional"))
    )
    (net (code "288") (name "unconnected-(U1B-IO,_(DQS3L{slash}CQ3L#,CDPCLK1){slash}(DQS3L{slash}CQ3L#,CDPCLK1){slash}(DQS3L{slash}CQ3L#,CDPCLK1)-PadT4)") (class "Default")
      (node (ref "U1") (pin "T4") (pinfunction "IO,_(DQS3L/CQ3L#,CDPCLK1)/(DQS3L/CQ3L#,CDPCLK1)/(DQS3L/CQ3L#,CDPCLK1)_T4") (pintype "bidirectional"))
    )
    (net (code "289") (name "unconnected-(U1B-IO,_DIFFIO_L22n,_(DQ1L){slash}(DQ3L){slash}(DQ1L)-PadN5)") (class "Default")
      (node (ref "U1") (pin "N5") (pinfunction "IO,_DIFFIO_L22n,_(DQ1L)/(DQ3L)/(DQ1L)_N5") (pintype "bidirectional"))
    )
    (net (code "290") (name "unconnected-(U1B-IO,_DIFFIO_L31n,_(DQ3L){slash}(DQ3L){slash}(DQ1L)-PadAA1)") (class "Default")
      (node (ref "U1") (pin "AA1") (pinfunction "IO,_DIFFIO_L31n,_(DQ3L)/(DQ3L)/(DQ1L)_AA1") (pintype "bidirectional"))
    )
    (net (code "291") (name "unconnected-(U1B-IO,_RDN1-PadV3)") (class "Default")
      (node (ref "U1") (pin "V3") (pinfunction "IO,_RDN1_V3") (pintype "bidirectional"))
    )
    (net (code "292") (name "unconnected-(U1B-IO,_RUP1-PadV4)") (class "Default")
      (node (ref "U1") (pin "V4") (pinfunction "IO,_RUP1_V4") (pintype "bidirectional"))
    )
    (net (code "293") (name "unconnected-(U1B-IO,_VREFB2N0-PadM5)") (class "Default")
      (node (ref "U1") (pin "M5") (pinfunction "IO,_VREFB2N0_M5") (pintype "bidirectional"))
    )
    (net (code "294") (name "unconnected-(U1B-IO,_VREFB2N1-PadT3)") (class "Default")
      (node (ref "U1") (pin "T3") (pinfunction "IO,_VREFB2N1_T3") (pintype "bidirectional"))
    )
    (net (code "295") (name "unconnected-(U1C-IO,_(DQ3B){slash}(DQ3B){slash}(DQ5B)-PadAA4)") (class "Default")
      (node (ref "U1") (pin "AA4") (pinfunction "IO,_(DQ3B)/(DQ3B)/(DQ5B)_AA4") (pintype "bidirectional"))
    )
    (net (code "296") (name "unconnected-(U1C-IO,_(DQ3B){slash}(DQ3B){slash}(DQ5B)-PadW8)") (class "Default")
      (node (ref "U1") (pin "W8") (pinfunction "IO,_(DQ3B)/(DQ3B)/(DQ5B)_W8") (pintype "bidirectional"))
    )
    (net (code "297") (name "unconnected-(U1C-IO,_(DQS1B{slash}CQ1B#,CDPCLK2){slash}(DQS1B{slash}CQ1B#,CDPCLK2){slash}(DQS1B{slash}CQ1B#,CDPCLK2)-PadY6)") (class "Default")
      (node (ref "U1") (pin "Y6") (pinfunction "IO,_(DQS1B/CQ1B#,CDPCLK2)/(DQS1B/CQ1B#,CDPCLK2)/(DQS1B/CQ1B#,CDPCLK2)_Y6") (pintype "bidirectional"))
    )
    (net (code "298") (name "unconnected-(U1C-IO,_DIFFIO_B1n,_(DM3B{slash}BWS#3B){slash}(DM3B{slash}BWS#3B){slash}(DM5B{slash}BWS#5B)-PadV5)") (class "Default")
      (node (ref "U1") (pin "V5") (pinfunction "IO,_DIFFIO_B1n,_(DM3B/BWS#3B)/(DM3B/BWS#3B)/(DM5B/BWS#5B)_V5") (pintype "bidirectional"))
    )
    (net (code "299") (name "unconnected-(U1C-IO,_DIFFIO_B1p-PadV6)") (class "Default")
      (node (ref "U1") (pin "V6") (pinfunction "IO,_DIFFIO_B1p_V6") (pintype "bidirectional"))
    )
    (net (code "300") (name "unconnected-(U1C-IO,_DIFFIO_B2n-PadU8)") (class "Default")
      (node (ref "U1") (pin "U8") (pinfunction "IO,_DIFFIO_B2n_U8") (pintype "bidirectional"))
    )
    (net (code "301") (name "unconnected-(U1C-IO,_DIFFIO_B2p-PadU7)") (class "Default")
      (node (ref "U1") (pin "U7") (pinfunction "IO,_DIFFIO_B2p_U7") (pintype "bidirectional"))
    )
    (net (code "302") (name "unconnected-(U1C-IO,_DIFFIO_B4n-PadV7)") (class "Default")
      (node (ref "U1") (pin "V7") (pinfunction "IO,_DIFFIO_B4n_V7") (pintype "bidirectional"))
    )
    (net (code "303") (name "unconnected-(U1C-IO,_DIFFIO_B4p,_(DQ3B){slash}(DQ3B){slash}(DQ5B)-PadW6)") (class "Default")
      (node (ref "U1") (pin "W6") (pinfunction "IO,_DIFFIO_B4p,_(DQ3B)/(DQ3B)/(DQ5B)_W6") (pintype "bidirectional"))
    )
    (net (code "304") (name "unconnected-(U1C-IO,_DIFFIO_B7n,_(DQ3B){slash}(DQ3B){slash}(DQ5B)-PadY7)") (class "Default")
      (node (ref "U1") (pin "Y7") (pinfunction "IO,_DIFFIO_B7n,_(DQ3B)/(DQ3B)/(DQ5B)_Y7") (pintype "bidirectional"))
    )
    (net (code "305") (name "unconnected-(U1C-IO,_DIFFIO_B7p,_(DQ3B){slash}(DQ3B){slash}(DQ5B)-PadW7)") (class "Default")
      (node (ref "U1") (pin "W7") (pinfunction "IO,_DIFFIO_B7p,_(DQ3B)/(DQ3B)/(DQ5B)_W7") (pintype "bidirectional"))
    )
    (net (code "306") (name "unconnected-(U1C-IO,_DIFFIO_B8n,_(DQ3B){slash}(DQ3B){slash}(DQ5B)-PadV8)") (class "Default")
      (node (ref "U1") (pin "V8") (pinfunction "IO,_DIFFIO_B8n,_(DQ3B)/(DQ3B)/(DQ5B)_V8") (pintype "bidirectional"))
    )
    (net (code "307") (name "unconnected-(U1C-IO,_DIFFIO_B8p,_(DQ3B){slash}(DQ3B){slash}(DQ5B)-PadU9)") (class "Default")
      (node (ref "U1") (pin "U9") (pinfunction "IO,_DIFFIO_B8p,_(DQ3B)/(DQ3B)/(DQ5B)_U9") (pintype "bidirectional"))
    )
    (net (code "308") (name "unconnected-(U1C-IO,_DIFFIO_B11p,_(DQ5B){slash}(DQ3B){slash}(DQ5B)-PadY8)") (class "Default")
      (node (ref "U1") (pin "Y8") (pinfunction "IO,_DIFFIO_B11p,_(DQ5B)/(DQ3B)/(DQ5B)_Y8") (pintype "bidirectional"))
    )
    (net (code "309") (name "unconnected-(U1C-IO,_DIFFIO_B13n-PadT11)") (class "Default")
      (node (ref "U1") (pin "T11") (pinfunction "IO,_DIFFIO_B13n_T11") (pintype "bidirectional"))
    )
    (net (code "310") (name "unconnected-(U1C-IO,_DIFFIO_B13p-PadT10)") (class "Default")
      (node (ref "U1") (pin "T10") (pinfunction "IO,_DIFFIO_B13p_T10") (pintype "bidirectional"))
    )
    (net (code "311") (name "unconnected-(U1C-IO,_DIFFIO_B15p,_(DQS3B{slash}CQ3B#,DPCLK2){slash}(DQS3B{slash}CQ3B#,DPCLK2){slash}(DQS3B{slash}CQ3B#,DPCLK2)-PadV10)") (class "Default")
      (node (ref "U1") (pin "V10") (pinfunction "IO,_DIFFIO_B15p,_(DQS3B/CQ3B#,DPCLK2)/(DQS3B/CQ3B#,DPCLK2)/(DQS3B/CQ3B#,DPCLK2)_V10") (pintype "bidirectional"))
    )
    (net (code "312") (name "unconnected-(U1C-IO,_DIFFIO_B16n,_(DQ5B){slash}(DQ3B){slash}(DQ5B)-PadU10)") (class "Default")
      (node (ref "U1") (pin "U10") (pinfunction "IO,_DIFFIO_B16n,_(DQ5B)/(DQ3B)/(DQ5B)_U10") (pintype "bidirectional"))
    )
    (net (code "313") (name "unconnected-(U1C-IO,_DIFFIO_B19n,_(DQ5B){slash}(DQ3B){slash}(DQ5B)-PadV11)") (class "Default")
      (node (ref "U1") (pin "V11") (pinfunction "IO,_DIFFIO_B19n,_(DQ5B)/(DQ3B)/(DQ5B)_V11") (pintype "bidirectional"))
    )
    (net (code "314") (name "unconnected-(U1C-IO,_DIFFIO_B19p-PadU11)") (class "Default")
      (node (ref "U1") (pin "U11") (pinfunction "IO,_DIFFIO_B19p_U11") (pintype "bidirectional"))
    )
    (net (code "315") (name "unconnected-(U1C-IO,_PLL1_CLKOUTn-PadAB3)") (class "Default")
      (node (ref "U1") (pin "AB3") (pinfunction "IO,_PLL1_CLKOUTn_AB3") (pintype "bidirectional"))
    )
    (net (code "316") (name "unconnected-(U1C-IO,_PLL1_CLKOUTp-PadAA3)") (class "Default")
      (node (ref "U1") (pin "AA3") (pinfunction "IO,_PLL1_CLKOUTp_AA3") (pintype "bidirectional"))
    )
    (net (code "317") (name "unconnected-(U1C-IO,_VREFB3N0-PadV9)") (class "Default")
      (node (ref "U1") (pin "V9") (pinfunction "IO,_VREFB3N0_V9") (pintype "bidirectional"))
    )
    (net (code "318") (name "unconnected-(U1C-IO,_VREFB3N1-PadAB4)") (class "Default")
      (node (ref "U1") (pin "AB4") (pinfunction "IO,_VREFB3N1_AB4") (pintype "bidirectional"))
    )
    (net (code "319") (name "unconnected-(U1D-IO,_(DQ2B){slash}(DQ5B){slash}(DQ5B)-PadAB18)") (class "Default")
      (node (ref "U1") (pin "AB18") (pinfunction "IO,_(DQ2B)/(DQ5B)/(DQ5B)_AB18") (pintype "bidirectional"))
    )
    (net (code "320") (name "unconnected-(U1D-IO,_DIFFIO_B28p,_(DQ4B){slash}(DQ5B){slash}(DQ5B)-PadU12)") (class "Default")
      (node (ref "U1") (pin "U12") (pinfunction "IO,_DIFFIO_B28p,_(DQ4B)/(DQ5B)/(DQ5B)_U12") (pintype "bidirectional"))
    )
    (net (code "321") (name "unconnected-(U1D-IO,_DIFFIO_B31p,_(DQS2B{slash}CQ3B,DPCLK5){slash}(DQS2B{slash}CQ3B,DPCLK5){slash}(DQS2B{slash}CQ3B,DPCLK5)-PadV13)") (class "Default")
      (node (ref "U1") (pin "V13") (pinfunction "IO,_DIFFIO_B31p,_(DQS2B/CQ3B,DPCLK5)/(DQS2B/CQ3B,DPCLK5)/(DQS2B/CQ3B,DPCLK5)_V13") (pintype "bidirectional"))
    )
    (net (code "322") (name "unconnected-(U1D-IO,_DIFFIO_B32p-PadU13)") (class "Default")
      (node (ref "U1") (pin "U13") (pinfunction "IO,_DIFFIO_B32p_U13") (pintype "bidirectional"))
    )
    (net (code "323") (name "unconnected-(U1D-IO,_DIFFIO_B33n-PadU14)") (class "Default")
      (node (ref "U1") (pin "U14") (pinfunction "IO,_DIFFIO_B33n_U14") (pintype "bidirectional"))
    )
    (net (code "324") (name "unconnected-(U1D-IO,_DIFFIO_B33p,_(DQ2B){slash}(DQ5B){slash}(DQ5B)-PadV14)") (class "Default")
      (node (ref "U1") (pin "V14") (pinfunction "IO,_DIFFIO_B33p,_(DQ2B)/(DQ5B)/(DQ5B)_V14") (pintype "bidirectional"))
    )
    (net (code "325") (name "unconnected-(U1D-IO,_DIFFIO_B34n,_(DQ2B){slash}(DQ5B){slash}(DQ5B)-PadV15)") (class "Default")
      (node (ref "U1") (pin "V15") (pinfunction "IO,_DIFFIO_B34n,_(DQ2B)/(DQ5B)/(DQ5B)_V15") (pintype "bidirectional"))
    )
    (net (code "326") (name "unconnected-(U1D-IO,_DIFFIO_B34p-PadU15)") (class "Default")
      (node (ref "U1") (pin "U15") (pinfunction "IO,_DIFFIO_B34p_U15") (pintype "bidirectional"))
    )
    (net (code "327") (name "unconnected-(U1D-IO,_DIFFIO_B36n,_(DQ2B){slash}(DQ5B){slash}(DQ5B)-PadT15)") (class "Default")
      (node (ref "U1") (pin "T15") (pinfunction "IO,_DIFFIO_B36n,_(DQ2B)/(DQ5B)/(DQ5B)_T15") (pintype "bidirectional"))
    )
    (net (code "328") (name "unconnected-(U1D-IO,_DIFFIO_B36p-PadT14)") (class "Default")
      (node (ref "U1") (pin "T14") (pinfunction "IO,_DIFFIO_B36p_T14") (pintype "bidirectional"))
    )
    (net (code "329") (name "unconnected-(U1D-IO,_DIFFIO_B37n-PadAB17)") (class "Default")
      (node (ref "U1") (pin "AB17") (pinfunction "IO,_DIFFIO_B37n_AB17") (pintype "bidirectional"))
    )
    (net (code "330") (name "unconnected-(U1D-IO,_DIFFIO_B37p-PadAA17)") (class "Default")
      (node (ref "U1") (pin "AA17") (pinfunction "IO,_DIFFIO_B37p_AA17") (pintype "bidirectional"))
    )
    (net (code "331") (name "unconnected-(U1D-IO,_DIFFIO_B38n,_(DQS0B{slash}CQ1B,CDPCLK3){slash}(DQS0B{slash}CQ1B,CDPCLK3){slash}(DQS0B{slash}CQ1B,CDPCLK3)-PadY17)") (class "Default")
      (node (ref "U1") (pin "Y17") (pinfunction "IO,_DIFFIO_B38n,_(DQS0B/CQ1B,CDPCLK3)/(DQS0B/CQ1B,CDPCLK3)/(DQS0B/CQ1B,CDPCLK3)_Y17") (pintype "bidirectional"))
    )
    (net (code "332") (name "unconnected-(U1D-IO,_DIFFIO_B38p,_(DQ2B){slash}(DQ5B){slash}(DQ5B)-PadW17)") (class "Default")
      (node (ref "U1") (pin "W17") (pinfunction "IO,_DIFFIO_B38p,_(DQ2B)/(DQ5B)/(DQ5B)_W17") (pintype "bidirectional"))
    )
    (net (code "333") (name "unconnected-(U1D-IO,_DIFFIO_B39n,_(DQ2B){slash}(DQ5B){slash}(DQ5B)-PadAB20)") (class "Default")
      (node (ref "U1") (pin "AB20") (pinfunction "IO,_DIFFIO_B39n,_(DQ2B)/(DQ5B)/(DQ5B)_AB20") (pintype "bidirectional"))
    )
    (net (code "334") (name "unconnected-(U1D-IO,_DIFFIO_B39p,__{slash}(DQ5B){slash}(DQ5B)-PadAA20)") (class "Default")
      (node (ref "U1") (pin "AA20") (pinfunction "IO,_DIFFIO_B39p,__/(DQ5B)/(DQ5B)_AA20") (pintype "bidirectional"))
    )
    (net (code "335") (name "unconnected-(U1D-IO,_DIFFIO_B40n-PadU17)") (class "Default")
      (node (ref "U1") (pin "U17") (pinfunction "IO,_DIFFIO_B40n_U17") (pintype "bidirectional"))
    )
    (net (code "336") (name "unconnected-(U1D-IO,_DIFFIO_B40p-PadU16)") (class "Default")
      (node (ref "U1") (pin "U16") (pinfunction "IO,_DIFFIO_B40p_U16") (pintype "bidirectional"))
    )
    (net (code "337") (name "unconnected-(U1D-IO,_DIFFIO_B41n-PadR15)") (class "Default")
      (node (ref "U1") (pin "R15") (pinfunction "IO,_DIFFIO_B41n_R15") (pintype "bidirectional"))
    )
    (net (code "338") (name "unconnected-(U1D-IO,_DIFFIO_B41p-PadR14)") (class "Default")
      (node (ref "U1") (pin "R14") (pinfunction "IO,_DIFFIO_B41p_R14") (pintype "bidirectional"))
    )
    (net (code "339") (name "unconnected-(U1D-IO,_PLL4_CLKOUTn-PadR16)") (class "Default")
      (node (ref "U1") (pin "R16") (pinfunction "IO,_PLL4_CLKOUTn_R16") (pintype "bidirectional"))
    )
    (net (code "340") (name "unconnected-(U1D-IO,_PLL4_CLKOUTp-PadT16)") (class "Default")
      (node (ref "U1") (pin "T16") (pinfunction "IO,_PLL4_CLKOUTp_T16") (pintype "bidirectional"))
    )
    (net (code "341") (name "unconnected-(U1D-IO,_RDN2-PadAB19)") (class "Default")
      (node (ref "U1") (pin "AB19") (pinfunction "IO,_RDN2_AB19") (pintype "bidirectional"))
    )
    (net (code "342") (name "unconnected-(U1D-IO,_RUP2-PadAA19)") (class "Default")
      (node (ref "U1") (pin "AA19") (pinfunction "IO,_RUP2_AA19") (pintype "bidirectional"))
    )
    (net (code "343") (name "unconnected-(U1D-IO,_VREFB4N0-PadAA18)") (class "Default")
      (node (ref "U1") (pin "AA18") (pinfunction "IO,_VREFB4N0_AA18") (pintype "bidirectional"))
    )
    (net (code "344") (name "unconnected-(U1D-IO,_VREFB4N1-PadV12)") (class "Default")
      (node (ref "U1") (pin "V12") (pinfunction "IO,_VREFB4N1_V12") (pintype "bidirectional"))
    )
    (net (code "345") (name "unconnected-(U1D-IO-PadV16)") (class "Default")
      (node (ref "U1") (pin "V16") (pinfunction "IO_V16") (pintype "bidirectional"))
    )
    (net (code "346") (name "unconnected-(U1E-IO,_(DQS3R{slash}CQ3R#,CDPCLK4){slash}(DQS3R{slash}CQ3R#,CDPCLK4){slash}(DQS3R{slash}CQ3R#,CDPCLK4)-PadW20)") (class "Default")
      (node (ref "U1") (pin "W20") (pinfunction "IO,_(DQS3R/CQ3R#,CDPCLK4)/(DQS3R/CQ3R#,CDPCLK4)/(DQS3R/CQ3R#,CDPCLK4)_W20") (pintype "bidirectional"))
    )
    (net (code "347") (name "unconnected-(U1E-IO,_DIFFIO_R25p-PadN16)") (class "Default")
      (node (ref "U1") (pin "N16") (pinfunction "IO,_DIFFIO_R25p_N16") (pintype "bidirectional"))
    )
    (net (code "348") (name "unconnected-(U1E-IO,_DIFFIO_R28n,_(DQ3R){slash}(DQ3R){slash}(DQ1R)-PadR20)") (class "Default")
      (node (ref "U1") (pin "R20") (pinfunction "IO,_DIFFIO_R28n,_(DQ3R)/(DQ3R)/(DQ1R)_R20") (pintype "bidirectional"))
    )
    (net (code "349") (name "unconnected-(U1E-IO,_DIFFIO_R30n-PadR17)") (class "Default")
      (node (ref "U1") (pin "R17") (pinfunction "IO,_DIFFIO_R30n_R17") (pintype "bidirectional"))
    )
    (net (code "350") (name "unconnected-(U1E-IO,_DIFFIO_R30p-PadP17)") (class "Default")
      (node (ref "U1") (pin "P17") (pinfunction "IO,_DIFFIO_R30p_P17") (pintype "bidirectional"))
    )
    (net (code "351") (name "unconnected-(U1E-IO,_RDN3-PadT18)") (class "Default")
      (node (ref "U1") (pin "T18") (pinfunction "IO,_RDN3_T18") (pintype "bidirectional"))
    )
    (net (code "352") (name "unconnected-(U1E-IO,_RUP3-PadT17)") (class "Default")
      (node (ref "U1") (pin "T17") (pinfunction "IO,_RUP3_T17") (pintype "bidirectional"))
    )
    (net (code "353") (name "unconnected-(U1E-IO,_VREFB5N0-PadP20)") (class "Default")
      (node (ref "U1") (pin "P20") (pinfunction "IO,_VREFB5N0_P20") (pintype "bidirectional"))
    )
    (net (code "354") (name "unconnected-(U1E-IO,_VREFB5N1-PadW19)") (class "Default")
      (node (ref "U1") (pin "W19") (pinfunction "IO,_VREFB5N1_W19") (pintype "bidirectional"))
    )
    (net (code "355") (name "unconnected-(U1E-IO-PadM16)") (class "Default")
      (node (ref "U1") (pin "M16") (pinfunction "IO_M16") (pintype "bidirectional"))
    )
    (net (code "356") (name "unconnected-(U1F-IO,_DIFFIO_R8n,_(nWE),_(DQ0R){slash}(DQ1R){slash}(DQ1R)-PadE22)") (class "Default")
      (node (ref "U1") (pin "E22") (pinfunction "IO,_DIFFIO_R8n,_(nWE),_(DQ0R)/(DQ1R)/(DQ1R)_E22") (pintype "bidirectional"))
    )
    (net (code "357") (name "unconnected-(U1F-IO,_DIFFIO_R8p,_(nOE),__{slash}(DQ1R){slash}(DQ1R)-PadE21)") (class "Default")
      (node (ref "U1") (pin "E21") (pinfunction "IO,_DIFFIO_R8p,_(nOE),__/(DQ1R)/(DQ1R)_E21") (pintype "bidirectional"))
    )
    (net (code "358") (name "unconnected-(U1F-IO,_DIFFIO_R12n-PadJ18)") (class "Default")
      (node (ref "U1") (pin "J18") (pinfunction "IO,_DIFFIO_R12n_J18") (pintype "bidirectional"))
    )
    (net (code "359") (name "unconnected-(U1F-IO,_DIFFIO_R16n,_(nCEO)-PadK22)") (class "Default")
      (node (ref "U1") (pin "K22") (pinfunction "IO,_DIFFIO_R16n,_(nCEO)_K22") (pintype "bidirectional"))
    )
    (net (code "360") (name "unconnected-(U1F-IO,_DIFFIO_R16p,_(CLKUSR)-PadK21)") (class "Default")
      (node (ref "U1") (pin "K21") (pinfunction "IO,_DIFFIO_R16p,_(CLKUSR)_K21") (pintype "bidirectional"))
    )
    (net (code "361") (name "unconnected-(U1F-IO,_DIFFIO_R17n,_(INIT_DONE)-PadL22)") (class "Default")
      (node (ref "U1") (pin "L22") (pinfunction "IO,_DIFFIO_R17n,_(INIT_DONE)_L22") (pintype "bidirectional"))
    )
    (net (code "362") (name "unconnected-(U1F-IO,_DIFFIO_R17p,_(CRC_ERROR)-PadL21)") (class "Default")
      (node (ref "U1") (pin "L21") (pinfunction "IO,_DIFFIO_R17p,_(CRC_ERROR)_L21") (pintype "bidirectional"))
    )
    (net (code "363") (name "unconnected-(U1F-IO,_VREFB6N0-PadH18)") (class "Default")
      (node (ref "U1") (pin "H18") (pinfunction "IO,_VREFB6N0_H18") (pintype "bidirectional"))
    )
    (net (code "364") (name "unconnected-(U1F-IO,_VREFB6N1-PadK19)") (class "Default")
      (node (ref "U1") (pin "K19") (pinfunction "IO,_VREFB6N1_K19") (pintype "bidirectional"))
    )
    (net (code "365") (name "unconnected-(U1F-IO-PadH16)") (class "Default")
      (node (ref "U1") (pin "H16") (pinfunction "IO_H16") (pintype "bidirectional"))
    )
    (net (code "366") (name "unconnected-(U1F-IO-PadJ17)") (class "Default")
      (node (ref "U1") (pin "J17") (pinfunction "IO_J17") (pintype "bidirectional"))
    )
    (net (code "367") (name "unconnected-(U1G-IO,_DIFFIO_T23n,_(PADD13)-PadE11)") (class "Default")
      (node (ref "U1") (pin "E11") (pinfunction "IO,_DIFFIO_T23n,_(PADD13)_E11") (pintype "bidirectional"))
    )
    (net (code "368") (name "unconnected-(U1G-IO,_DIFFIO_T23p,_(PADD14),_(DM4T){slash}(DM5T{slash}BWS#5T){slash}(DM5T{slash}BWS#5T)-PadF11)") (class "Default")
      (node (ref "U1") (pin "F11") (pinfunction "IO,_DIFFIO_T23p,_(PADD14),_(DM4T)/(DM5T/BWS#5T)/(DM5T/BWS#5T)_F11") (pintype "bidirectional"))
    )
    (net (code "369") (name "unconnected-(U1G-IO,_DIFFIO_T25p,_(PADD10),_(DQ4T){slash}(DQ5T){slash}(DQ5T)-PadB14)") (class "Default")
      (node (ref "U1") (pin "B14") (pinfunction "IO,_DIFFIO_T25p,_(PADD10),_(DQ4T)/(DQ5T)/(DQ5T)_B14") (pintype "bidirectional"))
    )
    (net (code "370") (name "unconnected-(U1G-IO,_DIFFIO_T26n,_(PADD7)-PadC13)") (class "Default")
      (node (ref "U1") (pin "C13") (pinfunction "IO,_DIFFIO_T26n,_(PADD7)_C13") (pintype "bidirectional"))
    )
    (net (code "371") (name "unconnected-(U1G-IO,_DIFFIO_T26p,_(PADD8),_(DQ4T){slash}(DQ5T){slash}(DQ5T)-PadD13)") (class "Default")
      (node (ref "U1") (pin "D13") (pinfunction "IO,_DIFFIO_T26p,_(PADD8),_(DQ4T)/(DQ5T)/(DQ5T)_D13") (pintype "bidirectional"))
    )
    (net (code "372") (name "unconnected-(U1G-IO,_DIFFIO_T28n,_(PADD3),_(DQ4T){slash}(DQ5T){slash}(DQ5T)-PadE14)") (class "Default")
      (node (ref "U1") (pin "E14") (pinfunction "IO,_DIFFIO_T28n,_(PADD3),_(DQ4T)/(DQ5T)/(DQ5T)_E14") (pintype "bidirectional"))
    )
    (net (code "373") (name "unconnected-(U1G-IO,_DIFFIO_T28p,_(PADD4),_(DQS2T{slash}CQ3T,DPCLK8){slash}(DQS2T{slash}CQ3T,DPCLK8){slash}(DQS2T{slash}CQ3T,DPCLK8)-PadF13)") (class "Default")
      (node (ref "U1") (pin "F13") (pinfunction "IO,_DIFFIO_T28p,_(PADD4),_(DQS2T/CQ3T,DPCLK8)/(DQS2T/CQ3T,DPCLK8)/(DQS2T/CQ3T,DPCLK8)_F13") (pintype "bidirectional"))
    )
    (net (code "374") (name "unconnected-(U1G-IO,_DIFFIO_T32n-PadG14)") (class "Default")
      (node (ref "U1") (pin "G14") (pinfunction "IO,_DIFFIO_T32n_G14") (pintype "bidirectional"))
    )
    (net (code "375") (name "unconnected-(U1G-IO,_DIFFIO_T32p-PadG13)") (class "Default")
      (node (ref "U1") (pin "G13") (pinfunction "IO,_DIFFIO_T32p_G13") (pintype "bidirectional"))
    )
    (net (code "376") (name "unconnected-(U1G-IO,_DIFFIO_T35p,_(DQ2T){slash}(DQ5T){slash}(DQ5T)-PadC17)") (class "Default")
      (node (ref "U1") (pin "C17") (pinfunction "IO,_DIFFIO_T35p,_(DQ2T)/(DQ5T)/(DQ5T)_C17") (pintype "bidirectional"))
    )
    (net (code "377") (name "unconnected-(U1G-IO,_DIFFIO_T40n-PadG15)") (class "Default")
      (node (ref "U1") (pin "G15") (pinfunction "IO,_DIFFIO_T40n_G15") (pintype "bidirectional"))
    )
    (net (code "378") (name "unconnected-(U1G-IO,_DIFFIO_T40p,_(DQS0T{slash}CQ1T,CDPCLK6){slash}(DQS0T{slash}CQ1T,CDPCLK6){slash}(DQS0T{slash}CQ1T,CDPCLK6)-PadF14)") (class "Default")
      (node (ref "U1") (pin "F14") (pinfunction "IO,_DIFFIO_T40p,_(DQS0T/CQ1T,CDPCLK6)/(DQS0T/CQ1T,CDPCLK6)/(DQS0T/CQ1T,CDPCLK6)_F14") (pintype "bidirectional"))
    )
    (net (code "379") (name "unconnected-(U1G-IO,_PLL2_CLKOUTn-PadA20)") (class "Default")
      (node (ref "U1") (pin "A20") (pinfunction "IO,_PLL2_CLKOUTn_A20") (pintype "bidirectional"))
    )
    (net (code "380") (name "unconnected-(U1G-IO,_PLL2_CLKOUTp-PadB20)") (class "Default")
      (node (ref "U1") (pin "B20") (pinfunction "IO,_PLL2_CLKOUTp_B20") (pintype "bidirectional"))
    )
    (net (code "381") (name "unconnected-(U1G-IO,_RDN4-PadA19)") (class "Default")
      (node (ref "U1") (pin "A19") (pinfunction "IO,_RDN4_A19") (pintype "bidirectional"))
    )
    (net (code "382") (name "unconnected-(U1G-IO,_RUP4-PadB19)") (class "Default")
      (node (ref "U1") (pin "B19") (pinfunction "IO,_RUP4_B19") (pintype "bidirectional"))
    )
    (net (code "383") (name "unconnected-(U1G-IO,_VREFB7N0-PadD17)") (class "Default")
      (node (ref "U1") (pin "D17") (pinfunction "IO,_VREFB7N0_D17") (pintype "bidirectional"))
    )
    (net (code "384") (name "unconnected-(U1G-IO,_VREFB7N1-PadC15)") (class "Default")
      (node (ref "U1") (pin "C15") (pinfunction "IO,_VREFB7N1_C15") (pintype "bidirectional"))
    )
    (net (code "385") (name "unconnected-(U1G-IO,__{slash}(DQ5T){slash}(DQ5T)-PadE12)") (class "Default")
      (node (ref "U1") (pin "E12") (pinfunction "IO,__/(DQ5T)/(DQ5T)_E12") (pintype "bidirectional"))
    )
    (net (code "386") (name "unconnected-(U1G-IO-PadE13)") (class "Default")
      (node (ref "U1") (pin "E13") (pinfunction "IO_E13") (pintype "bidirectional"))
    )
    (net (code "387") (name "unconnected-(U1H-IO,_DIFFIO_T2n,_(DM3T{slash}BWS#3T){slash}(DM3T{slash}BWS#3T){slash}(DM5T{slash}BWS#5T)-PadF7)") (class "Default")
      (node (ref "U1") (pin "F7") (pinfunction "IO,_DIFFIO_T2n,_(DM3T/BWS#3T)/(DM3T/BWS#3T)/(DM5T/BWS#5T)_F7") (pintype "bidirectional"))
    )
    (net (code "388") (name "unconnected-(U1H-IO,_DIFFIO_T2p-PadG7)") (class "Default")
      (node (ref "U1") (pin "G7") (pinfunction "IO,_DIFFIO_T2p_G7") (pintype "bidirectional"))
    )
    (net (code "389") (name "unconnected-(U1H-IO,_DIFFIO_T4n-PadD6)") (class "Default")
      (node (ref "U1") (pin "D6") (pinfunction "IO,_DIFFIO_T4n_D6") (pintype "bidirectional"))
    )
    (net (code "390") (name "unconnected-(U1H-IO,_DIFFIO_T4p-PadE7)") (class "Default")
      (node (ref "U1") (pin "E7") (pinfunction "IO,_DIFFIO_T4p_E7") (pintype "bidirectional"))
    )
    (net (code "391") (name "unconnected-(U1H-IO,_DIFFIO_T7n,_(DATA9),_(DQ3T){slash}(DQ3T){slash}(DQ5T)-PadF8)") (class "Default")
      (node (ref "U1") (pin "F8") (pinfunction "IO,_DIFFIO_T7n,_(DATA9),_(DQ3T)/(DQ3T)/(DQ5T)_F8") (pintype "bidirectional"))
    )
    (net (code "392") (name "unconnected-(U1H-IO,_DIFFIO_T7p-PadG8)") (class "Default")
      (node (ref "U1") (pin "G8") (pinfunction "IO,_DIFFIO_T7p_G8") (pintype "bidirectional"))
    )
    (net (code "393") (name "unconnected-(U1H-IO,_DIFFIO_T9n,_(DATA7),_(DQ3T){slash}(DQ3T){slash}(DQ5T)-PadC6)") (class "Default")
      (node (ref "U1") (pin "C6") (pinfunction "IO,_DIFFIO_T9n,_(DATA7),_(DQ3T)/(DQ3T)/(DQ5T)_C6") (pintype "bidirectional"))
    )
    (net (code "394") (name "unconnected-(U1H-IO,_DIFFIO_T9p-PadD7)") (class "Default")
      (node (ref "U1") (pin "D7") (pinfunction "IO,_DIFFIO_T9p_D7") (pintype "bidirectional"))
    )
    (net (code "395") (name "unconnected-(U1H-IO,_DIFFIO_T10n-PadG10)") (class "Default")
      (node (ref "U1") (pin "G10") (pinfunction "IO,_DIFFIO_T10n_G10") (pintype "bidirectional"))
    )
    (net (code "396") (name "unconnected-(U1H-IO,_DIFFIO_T10p,_(DATA6),_(DQ3T){slash}(DQ3T){slash}(DQ5T)-PadF10)") (class "Default")
      (node (ref "U1") (pin "F10") (pinfunction "IO,_DIFFIO_T10p,_(DATA6),_(DQ3T)/(DQ3T)/(DQ5T)_F10") (pintype "bidirectional"))
    )
    (net (code "397") (name "unconnected-(U1H-IO,_DIFFIO_T14n-PadE9)") (class "Default")
      (node (ref "U1") (pin "E9") (pinfunction "IO,_DIFFIO_T14n_E9") (pintype "bidirectional"))
    )
    (net (code "398") (name "unconnected-(U1H-IO,_DIFFIO_T18n-PadG11)") (class "Default")
      (node (ref "U1") (pin "G11") (pinfunction "IO,_DIFFIO_T18n_G11") (pintype "bidirectional"))
    )
    (net (code "399") (name "unconnected-(U1H-IO,_DIFFIO_T22n,_(DQ5T){slash}(DQ3T){slash}(DQ5T)-PadD10)") (class "Default")
      (node (ref "U1") (pin "D10") (pinfunction "IO,_DIFFIO_T22n,_(DQ5T)/(DQ3T)/(DQ5T)_D10") (pintype "bidirectional"))
    )
    (net (code "400") (name "unconnected-(U1H-IO,_DIFFIO_T22p-PadE10)") (class "Default")
      (node (ref "U1") (pin "E10") (pinfunction "IO,_DIFFIO_T22p_E10") (pintype "bidirectional"))
    )
    (net (code "401") (name "unconnected-(U1H-IO,_PLL3_CLKOUTn-PadE6)") (class "Default")
      (node (ref "U1") (pin "E6") (pinfunction "IO,_PLL3_CLKOUTn_E6") (pintype "bidirectional"))
    )
    (net (code "402") (name "unconnected-(U1H-IO,_PLL3_CLKOUTp-PadE5)") (class "Default")
      (node (ref "U1") (pin "E5") (pinfunction "IO,_PLL3_CLKOUTp_E5") (pintype "bidirectional"))
    )
    (net (code "403") (name "unconnected-(U1H-IO,_VREFB8N0-PadC10)") (class "Default")
      (node (ref "U1") (pin "C10") (pinfunction "IO,_VREFB8N0_C10") (pintype "bidirectional"))
    )
    (net (code "404") (name "unconnected-(U1H-IO,_VREFB8N1-PadB5)") (class "Default")
      (node (ref "U1") (pin "B5") (pinfunction "IO,_VREFB8N1_B5") (pintype "bidirectional"))
    )
    (net (code "405") (name "unconnected-(U1H-IO-PadF9)") (class "Default")
      (node (ref "U1") (pin "F9") (pinfunction "IO_F9") (pintype "bidirectional"))
    )
    (net (code "406") (name "unconnected-(U1J-TDO-PadL4)") (class "Default")
      (node (ref "U1") (pin "L4") (pinfunction "TDO_L4") (pintype "output"))
    )
    (net (code "407") (name "unconnected-(UL1A-DATA-Pad1)") (class "Default")
      (node (ref "UL1") (pin "1") (pinfunction "DATA_1") (pintype "bidirectional"))
    )
    (net (code "408") (name "unconnected-(UL1A-GND-Pad5)") (class "Default")
      (node (ref "UL1") (pin "5") (pinfunction "GND_5") (pintype "passive"))
    )
    (net (code "409") (name "unconnected-(UL1A-WIRE+-Pad13)") (class "Default")
      (node (ref "UL1") (pin "13") (pinfunction "WIRE+_13") (pintype "bidirectional"))
    )
  )
)
